# RX08c.net
KiCad netlist of a schematic drawn in EAGLE
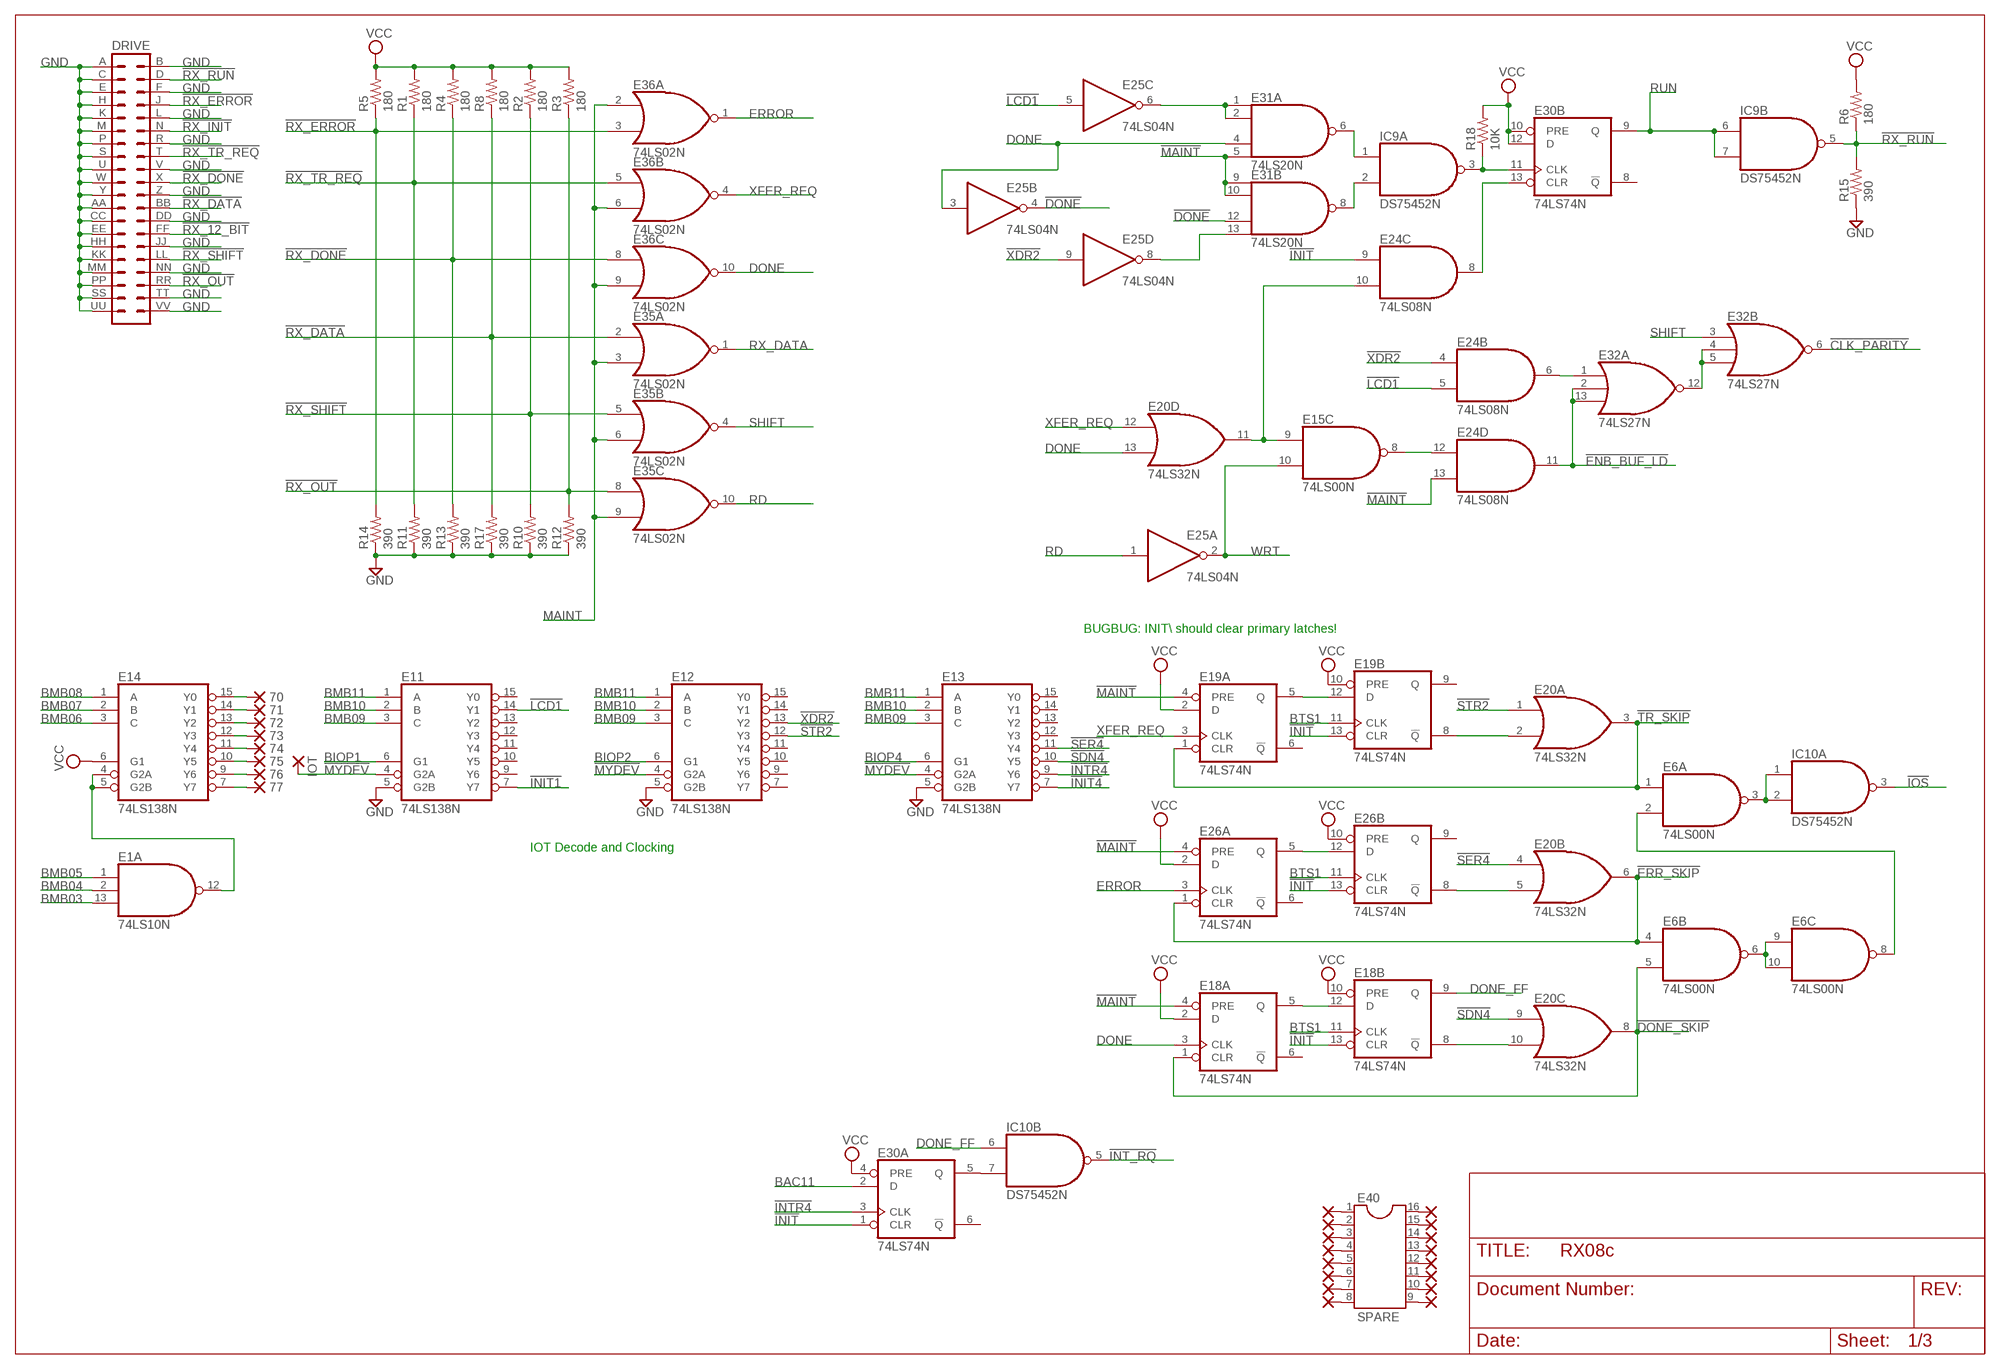
[diagram p0: schematic, sheet 1]
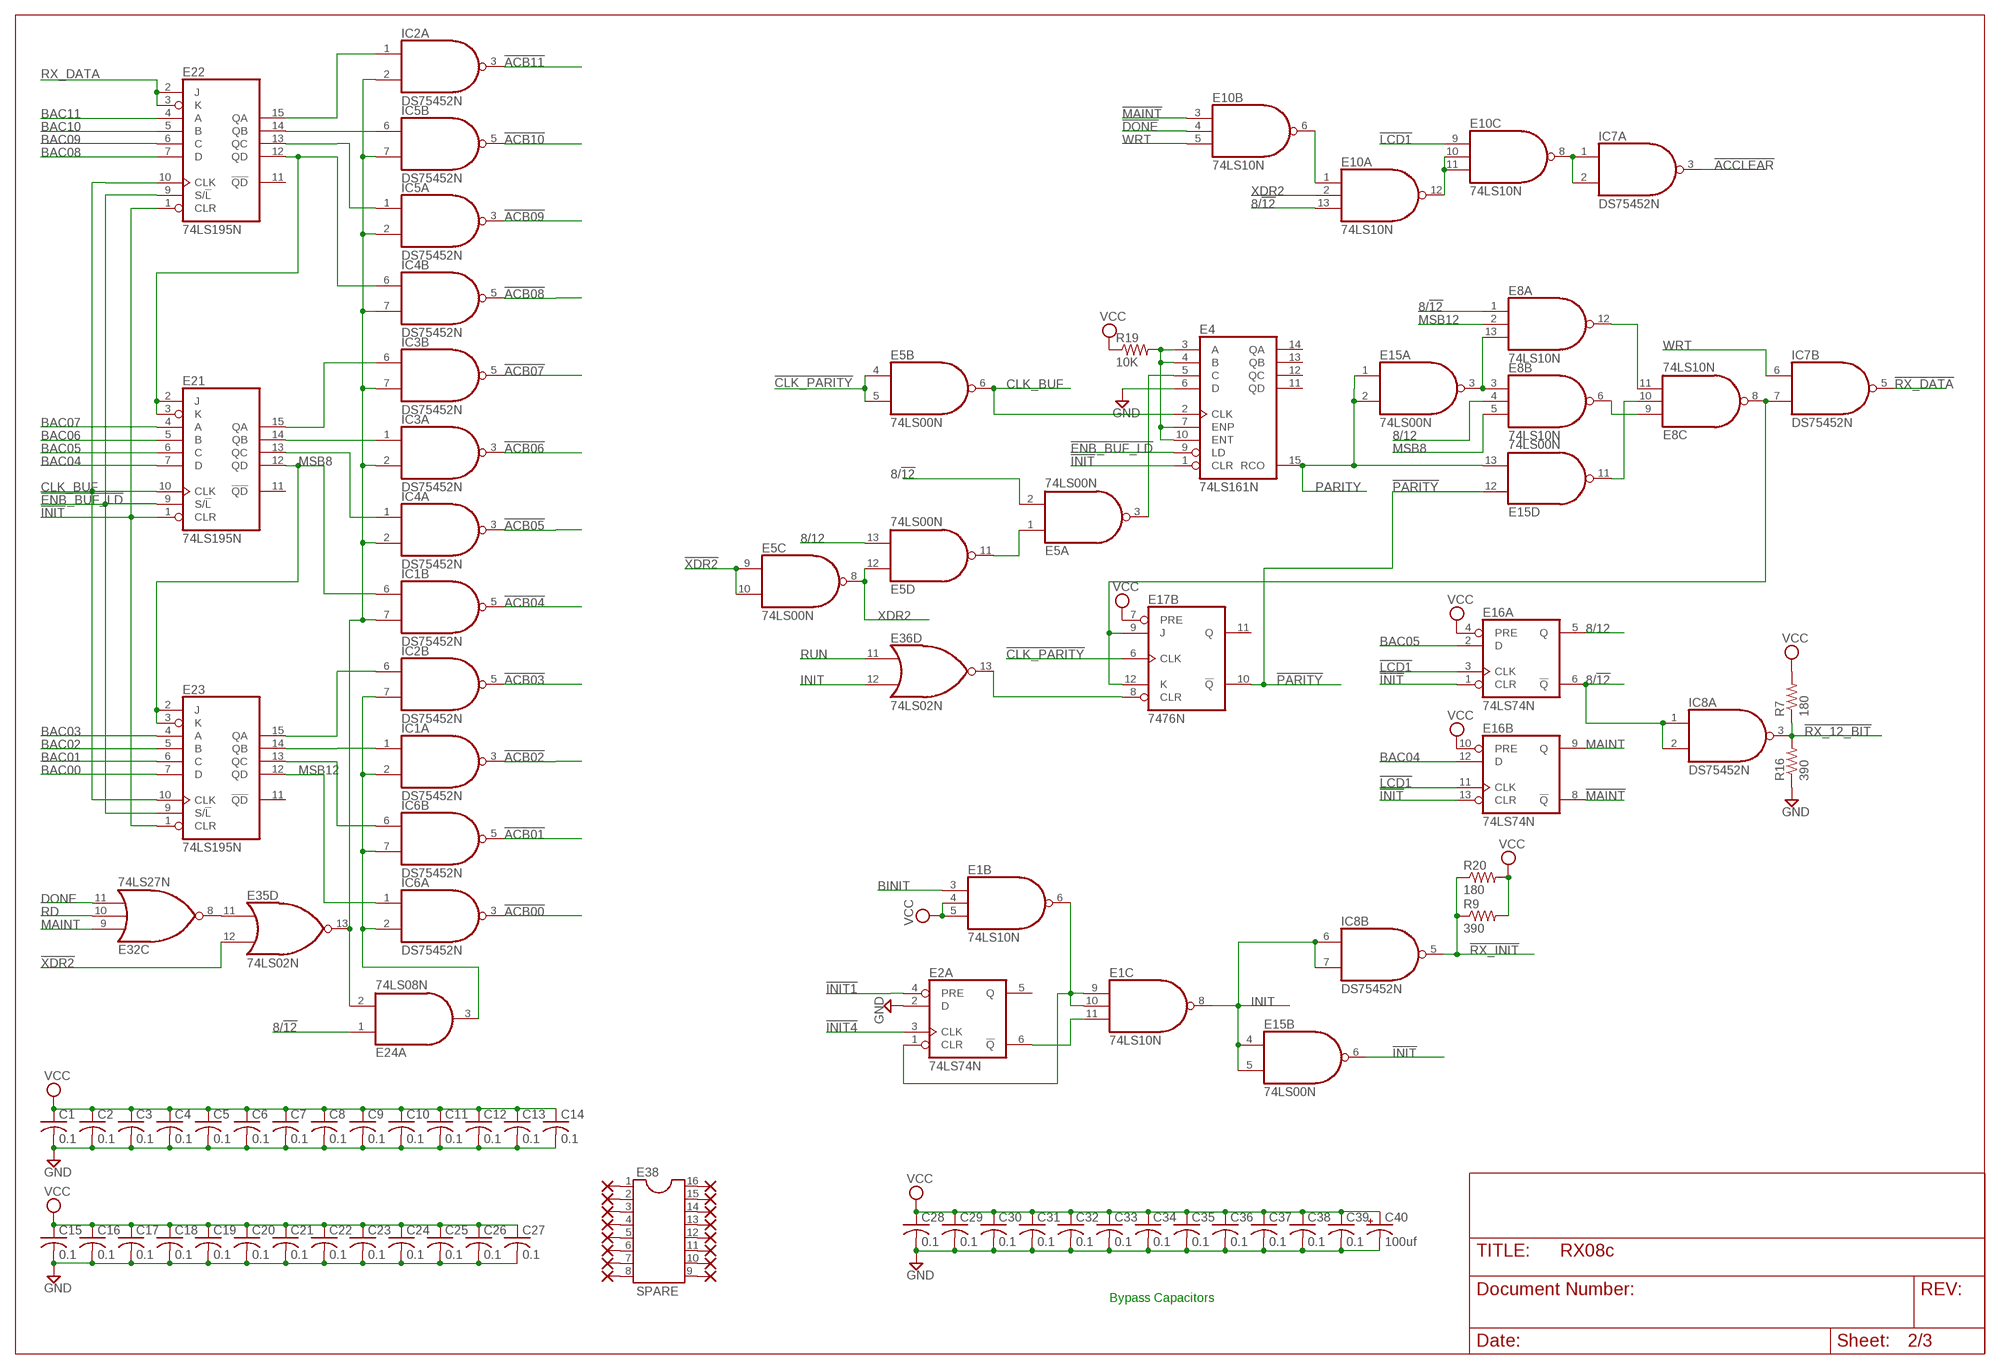
[diagram p1: schematic, sheet 2]
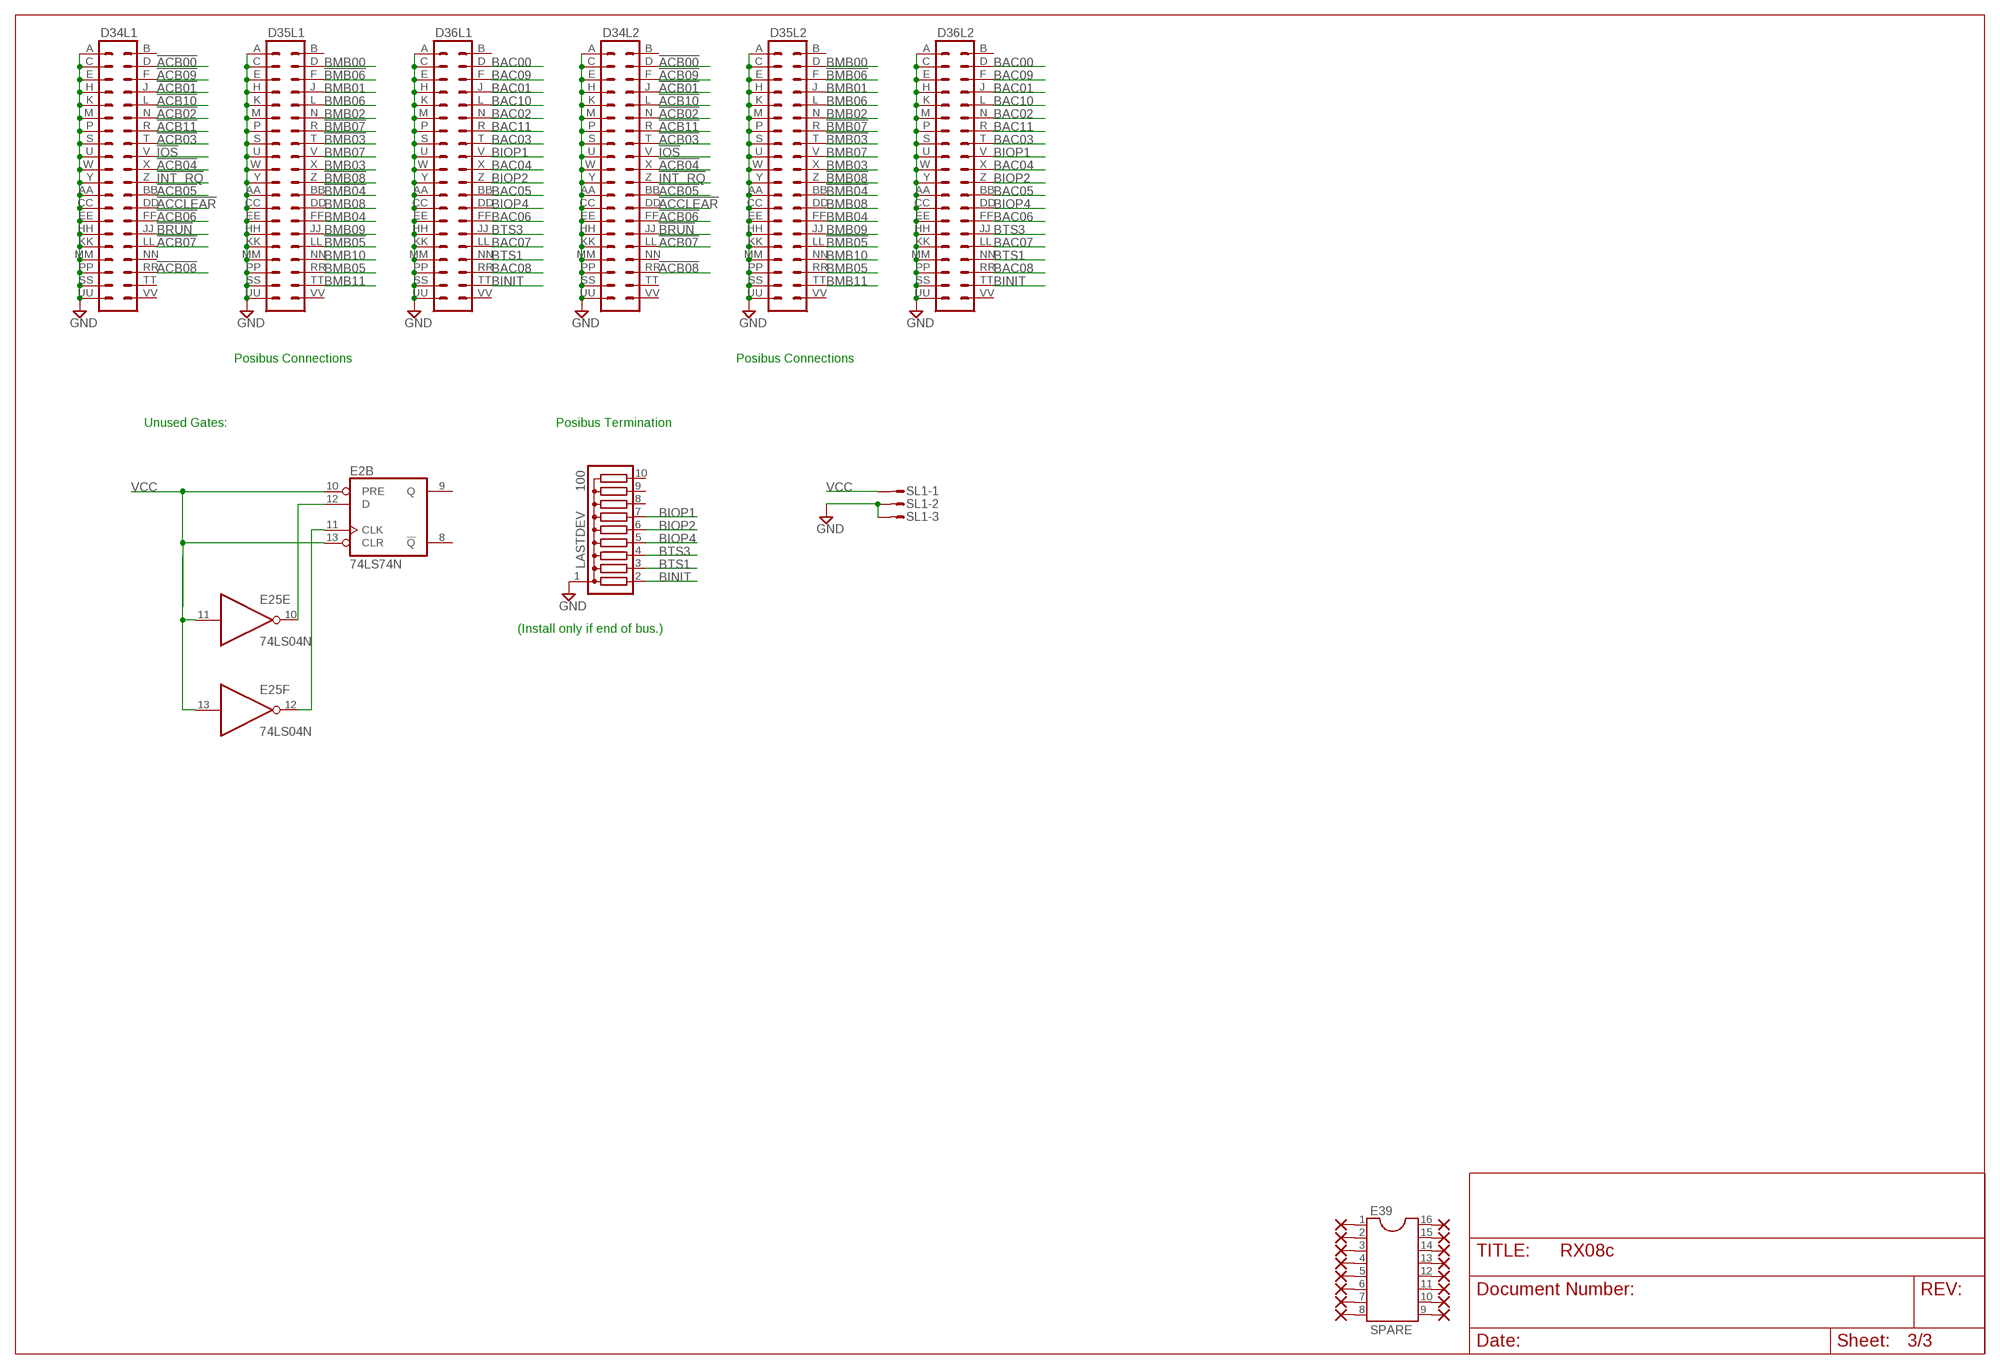
[diagram p2: schematic, sheet 3]

(export (version "E")
  (design (tool "Eeschema 10.0.6"))
  (components
    (comp (ref "C1")
      (value "0.1")
      (footprint "eagle-import:C050-025X075")
      (libsource (lib "eagle-import") (part "C-US050-025X075"))
    )
    (comp (ref "C2")
      (value "0.1")
      (footprint "eagle-import:C050-025X075")
      (libsource (lib "eagle-import") (part "C-US050-025X075"))
    )
    (comp (ref "C3")
      (value "0.1")
      (footprint "eagle-import:C050-025X075")
      (libsource (lib "eagle-import") (part "C-US050-025X075"))
    )
    (comp (ref "C4")
      (value "0.1")
      (footprint "eagle-import:C050-025X075")
      (libsource (lib "eagle-import") (part "C-US050-025X075"))
    )
    (comp (ref "C5")
      (value "0.1")
      (footprint "eagle-import:C050-025X075")
      (libsource (lib "eagle-import") (part "C-US050-025X075"))
    )
    (comp (ref "C6")
      (value "0.1")
      (footprint "eagle-import:C050-025X075")
      (libsource (lib "eagle-import") (part "C-US050-025X075"))
    )
    (comp (ref "C7")
      (value "0.1")
      (footprint "eagle-import:C050-025X075")
      (libsource (lib "eagle-import") (part "C-US050-025X075"))
    )
    (comp (ref "C8")
      (value "0.1")
      (footprint "eagle-import:C050-025X075")
      (libsource (lib "eagle-import") (part "C-US050-025X075"))
    )
    (comp (ref "C9")
      (value "0.1")
      (footprint "eagle-import:C050-025X075")
      (libsource (lib "eagle-import") (part "C-US050-025X075"))
    )
    (comp (ref "C10")
      (value "0.1")
      (footprint "eagle-import:C050-025X075")
      (libsource (lib "eagle-import") (part "C-US050-025X075"))
    )
    (comp (ref "C11")
      (value "0.1")
      (footprint "eagle-import:C050-025X075")
      (libsource (lib "eagle-import") (part "C-US050-025X075"))
    )
    (comp (ref "C12")
      (value "0.1")
      (footprint "eagle-import:C050-025X075")
      (libsource (lib "eagle-import") (part "C-US050-025X075"))
    )
    (comp (ref "C13")
      (value "0.1")
      (footprint "eagle-import:C050-025X075")
      (libsource (lib "eagle-import") (part "C-US050-025X075"))
    )
    (comp (ref "C14")
      (value "0.1")
      (footprint "eagle-import:C050-025X075")
      (libsource (lib "eagle-import") (part "C-US050-025X075"))
    )
    (comp (ref "C15")
      (value "0.1")
      (footprint "eagle-import:C050-025X075")
      (libsource (lib "eagle-import") (part "C-US050-025X075"))
    )
    (comp (ref "C16")
      (value "0.1")
      (footprint "eagle-import:C050-025X075")
      (libsource (lib "eagle-import") (part "C-US050-025X075"))
    )
    (comp (ref "C17")
      (value "0.1")
      (footprint "eagle-import:C050-025X075")
      (libsource (lib "eagle-import") (part "C-US050-025X075"))
    )
    (comp (ref "C18")
      (value "0.1")
      (footprint "eagle-import:C050-025X075")
      (libsource (lib "eagle-import") (part "C-US050-025X075"))
    )
    (comp (ref "C19")
      (value "0.1")
      (footprint "eagle-import:C050-025X075")
      (libsource (lib "eagle-import") (part "C-US050-025X075"))
    )
    (comp (ref "C20")
      (value "0.1")
      (footprint "eagle-import:C050-025X075")
      (libsource (lib "eagle-import") (part "C-US050-025X075"))
    )
    (comp (ref "C21")
      (value "0.1")
      (footprint "eagle-import:C050-025X075")
      (libsource (lib "eagle-import") (part "C-US050-025X075"))
    )
    (comp (ref "C22")
      (value "0.1")
      (footprint "eagle-import:C050-025X075")
      (libsource (lib "eagle-import") (part "C-US050-025X075"))
    )
    (comp (ref "C23")
      (value "0.1")
      (footprint "eagle-import:C050-025X075")
      (libsource (lib "eagle-import") (part "C-US050-025X075"))
    )
    (comp (ref "C24")
      (value "0.1")
      (footprint "eagle-import:C050-025X075")
      (libsource (lib "eagle-import") (part "C-US050-025X075"))
    )
    (comp (ref "C25")
      (value "0.1")
      (footprint "eagle-import:C050-025X075")
      (libsource (lib "eagle-import") (part "C-US050-025X075"))
    )
    (comp (ref "C26")
      (value "0.1")
      (footprint "eagle-import:C050-025X075")
      (libsource (lib "eagle-import") (part "C-US050-025X075"))
    )
    (comp (ref "C27")
      (value "0.1")
      (footprint "eagle-import:C050-025X075")
      (libsource (lib "eagle-import") (part "C-US050-025X075"))
    )
    (comp (ref "C28")
      (value "0.1")
      (footprint "eagle-import:C050-025X075")
      (libsource (lib "eagle-import") (part "C-US050-025X075"))
    )
    (comp (ref "C29")
      (value "0.1")
      (footprint "eagle-import:C050-025X075")
      (libsource (lib "eagle-import") (part "C-US050-025X075"))
    )
    (comp (ref "C30")
      (value "0.1")
      (footprint "eagle-import:C050-025X075")
      (libsource (lib "eagle-import") (part "C-US050-025X075"))
    )
    (comp (ref "C31")
      (value "0.1")
      (footprint "eagle-import:C050-025X075")
      (libsource (lib "eagle-import") (part "C-US050-025X075"))
    )
    (comp (ref "C32")
      (value "0.1")
      (footprint "eagle-import:C050-025X075")
      (libsource (lib "eagle-import") (part "C-US050-025X075"))
    )
    (comp (ref "C33")
      (value "0.1")
      (footprint "eagle-import:C050-025X075")
      (libsource (lib "eagle-import") (part "C-US050-025X075"))
    )
    (comp (ref "C34")
      (value "0.1")
      (footprint "eagle-import:C050-025X075")
      (libsource (lib "eagle-import") (part "C-US050-025X075"))
    )
    (comp (ref "C35")
      (value "0.1")
      (footprint "eagle-import:C050-025X075")
      (libsource (lib "eagle-import") (part "C-US050-025X075"))
    )
    (comp (ref "C36")
      (value "0.1")
      (footprint "eagle-import:C050-025X075")
      (libsource (lib "eagle-import") (part "C-US050-025X075"))
    )
    (comp (ref "C37")
      (value "0.1")
      (footprint "eagle-import:C050-025X075")
      (libsource (lib "eagle-import") (part "C-US050-025X075"))
    )
    (comp (ref "C38")
      (value "0.1")
      (footprint "eagle-import:C050-025X075")
      (libsource (lib "eagle-import") (part "C-US050-025X075"))
    )
    (comp (ref "C39")
      (value "0.1")
      (footprint "eagle-import:C050-025X075")
      (libsource (lib "eagle-import") (part "C-US050-025X075"))
    )
    (comp (ref "C40")
      (value "100uf")
      (footprint "eagle-import:E22-9")
      (libsource (lib "eagle-import") (part "CPOL-USE22-9AXIAL"))
    )
    (comp (ref "E1")
      (value "74LS10N")
      (footprint "eagle-import:DIL14")
      (libsource (lib "eagle-import") (part "7410NLS"))
    )
    (comp (ref "E2")
      (value "74LS74N")
      (footprint "eagle-import:DIL14")
      (libsource (lib "eagle-import") (part "7474NLS"))
    )
    (comp (ref "E4")
      (value "74LS161N")
      (footprint "eagle-import:DIL16")
      (libsource (lib "eagle-import") (part "74161NLS"))
    )
    (comp (ref "E5")
      (value "74LS00N")
      (footprint "eagle-import:DIL14")
      (libsource (lib "eagle-import") (part "7400NLS"))
    )
    (comp (ref "E8")
      (value "74LS10N")
      (footprint "eagle-import:DIL14")
      (libsource (lib "eagle-import") (part "7410NLS"))
    )
    (comp (ref "E10")
      (value "74LS10N")
      (footprint "eagle-import:DIL14")
      (libsource (lib "eagle-import") (part "7410NLS"))
    )
    (comp (ref "E15")
      (value "74LS00N")
      (footprint "eagle-import:DIL14")
      (libsource (lib "eagle-import") (part "7400NLS"))
    )
    (comp (ref "E16")
      (value "74LS74N")
      (footprint "eagle-import:DIL14")
      (libsource (lib "eagle-import") (part "7474NLS"))
    )
    (comp (ref "E17")
      (value "7476N")
      (footprint "eagle-import:DIL16")
      (libsource (lib "eagle-import") (part "7476N"))
    )
    (comp (ref "E21")
      (value "74LS195N")
      (footprint "eagle-import:DIL16")
      (libsource (lib "eagle-import") (part "74195NLS"))
    )
    (comp (ref "E22")
      (value "74LS195N")
      (footprint "eagle-import:DIL16")
      (libsource (lib "eagle-import") (part "74195NLS"))
    )
    (comp (ref "E23")
      (value "74LS195N")
      (footprint "eagle-import:DIL16")
      (libsource (lib "eagle-import") (part "74195NLS"))
    )
    (comp (ref "E24")
      (value "74LS08N")
      (footprint "eagle-import:DIL14")
      (libsource (lib "eagle-import") (part "7408NLS"))
    )
    (comp (ref "E32")
      (value "74LS27N")
      (footprint "eagle-import:DIL14")
      (libsource (lib "eagle-import") (part "7427NLS"))
    )
    (comp (ref "E35")
      (value "74LS02N")
      (footprint "eagle-import:DIL14")
      (libsource (lib "eagle-import") (part "7402NLS"))
    )
    (comp (ref "E36")
      (value "74LS02N")
      (footprint "eagle-import:DIL14")
      (libsource (lib "eagle-import") (part "7402NLS"))
    )
    (comp (ref "E38")
      (value "SPARE")
      (footprint "eagle-import:DIL16")
      (libsource (lib "eagle-import") (part "DIL16"))
    )
    (comp (ref "IC1")
      (value "DS75452N")
      (footprint "eagle-import:DIL08")
      (libsource (lib "eagle-import") (part "DS75452N"))
    )
    (comp (ref "IC2")
      (value "DS75452N")
      (footprint "eagle-import:DIL08")
      (libsource (lib "eagle-import") (part "DS75452N"))
    )
    (comp (ref "IC3")
      (value "DS75452N")
      (footprint "eagle-import:DIL08")
      (libsource (lib "eagle-import") (part "DS75452N"))
    )
    (comp (ref "IC4")
      (value "DS75452N")
      (footprint "eagle-import:DIL08")
      (libsource (lib "eagle-import") (part "DS75452N"))
    )
    (comp (ref "IC5")
      (value "DS75452N")
      (footprint "eagle-import:DIL08")
      (libsource (lib "eagle-import") (part "DS75452N"))
    )
    (comp (ref "IC6")
      (value "DS75452N")
      (footprint "eagle-import:DIL08")
      (libsource (lib "eagle-import") (part "DS75452N"))
    )
    (comp (ref "IC7")
      (value "DS75452N")
      (footprint "eagle-import:DIL08")
      (libsource (lib "eagle-import") (part "DS75452N"))
    )
    (comp (ref "IC8")
      (value "DS75452N")
      (footprint "eagle-import:DIL08")
      (libsource (lib "eagle-import") (part "DS75452N"))
    )
    (comp (ref "PAD10")
      (value "1,6/0,8")
      (footprint "eagle-import:1,6_0,8")
      (libsource (lib "eagle-import") (part "1,6/0,8"))
    )
    (comp (ref "PAD11")
      (value "1,6/0,8")
      (footprint "eagle-import:1,6_0,8")
      (libsource (lib "eagle-import") (part "1,6/0,8"))
    )
    (comp (ref "PAD12")
      (value "1,6/0,8")
      (footprint "eagle-import:1,6_0,8")
      (libsource (lib "eagle-import") (part "1,6/0,8"))
    )
    (comp (ref "PAD13")
      (value "1,6/0,8")
      (footprint "eagle-import:1,6_0,8")
      (libsource (lib "eagle-import") (part "1,6/0,8"))
    )
    (comp (ref "PAD14")
      (value "1,6/0,8")
      (footprint "eagle-import:1,6_0,8")
      (libsource (lib "eagle-import") (part "1,6/0,8"))
    )
    (comp (ref "PAD15")
      (value "1,6/0,8")
      (footprint "eagle-import:1,6_0,8")
      (libsource (lib "eagle-import") (part "1,6/0,8"))
    )
    (comp (ref "PAD16")
      (value "1,6/0,8")
      (footprint "eagle-import:1,6_0,8")
      (libsource (lib "eagle-import") (part "1,6/0,8"))
    )
    (comp (ref "PAD17")
      (value "1,6/0,8")
      (footprint "eagle-import:1,6_0,8")
      (libsource (lib "eagle-import") (part "1,6/0,8"))
    )
    (comp (ref "PAD20")
      (value "1,6/0,8")
      (footprint "eagle-import:1,6_0,8")
      (libsource (lib "eagle-import") (part "1,6/0,8"))
    )
    (comp (ref "PAD21")
      (value "1,6/0,8")
      (footprint "eagle-import:1,6_0,8")
      (libsource (lib "eagle-import") (part "1,6/0,8"))
    )
    (comp (ref "PAD22")
      (value "1,6/0,8")
      (footprint "eagle-import:1,6_0,8")
      (libsource (lib "eagle-import") (part "1,6/0,8"))
    )
    (comp (ref "PAD23")
      (value "1,6/0,8")
      (footprint "eagle-import:1,6_0,8")
      (libsource (lib "eagle-import") (part "1,6/0,8"))
    )
    (comp (ref "PAD24")
      (value "1,6/0,8")
      (footprint "eagle-import:1,6_0,8")
      (libsource (lib "eagle-import") (part "1,6/0,8"))
    )
    (comp (ref "PAD25")
      (value "1,6/0,8")
      (footprint "eagle-import:1,6_0,8")
      (libsource (lib "eagle-import") (part "1,6/0,8"))
    )
    (comp (ref "PAD26")
      (value "1,6/0,8")
      (footprint "eagle-import:1,6_0,8")
      (libsource (lib "eagle-import") (part "1,6/0,8"))
    )
    (comp (ref "PAD27")
      (value "1,6/0,8")
      (footprint "eagle-import:1,6_0,8")
      (libsource (lib "eagle-import") (part "1,6/0,8"))
    )
    (comp (ref "R7")
      (value "180")
      (footprint "eagle-import:0207_10")
      (libsource (lib "eagle-import") (part "R-US_0207/10"))
    )
    (comp (ref "R9")
      (value "390")
      (footprint "eagle-import:0207_10")
      (libsource (lib "eagle-import") (part "R-US_0207/10"))
    )
    (comp (ref "R16")
      (value "390")
      (footprint "eagle-import:0207_10")
      (libsource (lib "eagle-import") (part "R-US_0207/10"))
    )
    (comp (ref "R19")
      (value "10K")
      (footprint "eagle-import:0207_10")
      (libsource (lib "eagle-import") (part "R-US_0207/10"))
    )
    (comp (ref "R20")
      (value "180")
      (footprint "eagle-import:0207_10")
      (libsource (lib "eagle-import") (part "R-US_0207/10"))
    )
    (comp (ref "D34L1")
      (value "DEC40PINV")
      (footprint "eagle-import:DEC40PINV")
      (libsource (lib "eagle-import") (part "DEC40PINV"))
    )
    (comp (ref "D34L2")
      (value "DEC40PINV")
      (footprint "eagle-import:DEC40PINV")
      (libsource (lib "eagle-import") (part "DEC40PINV"))
    )
    (comp (ref "D35L1")
      (value "DEC40PINV")
      (footprint "eagle-import:DEC40PINV")
      (libsource (lib "eagle-import") (part "DEC40PINV"))
    )
    (comp (ref "D35L2")
      (value "DEC40PINV")
      (footprint "eagle-import:DEC40PINV")
      (libsource (lib "eagle-import") (part "DEC40PINV"))
    )
    (comp (ref "D36L1")
      (value "DEC40PINV")
      (footprint "eagle-import:DEC40PINV")
      (libsource (lib "eagle-import") (part "DEC40PINV"))
    )
    (comp (ref "D36L2")
      (value "DEC40PINV")
      (footprint "eagle-import:DEC40PINV")
      (libsource (lib "eagle-import") (part "DEC40PINV"))
    )
    (comp (ref "E25")
      (value "74LS04N")
      (footprint "eagle-import:DIL14")
      (libsource (lib "eagle-import") (part "7404NLS"))
    )
    (comp (ref "E39")
      (value "SPARE")
      (footprint "eagle-import:DIL16")
      (libsource (lib "eagle-import") (part "DIL16"))
    )
    (comp (ref "LASTDEV")
      (value "100")
      (footprint "eagle-import:SIL10")
      (libsource (lib "eagle-import") (part "G09R"))
    )
    (comp (ref "PAD42")
      (value "1,6/0,8")
      (footprint "eagle-import:1,6_0,8")
      (libsource (lib "eagle-import") (part "1,6/0,8"))
    )
    (comp (ref "PAD43")
      (value "1,6/0,8")
      (footprint "eagle-import:1,6_0,8")
      (libsource (lib "eagle-import") (part "1,6/0,8"))
    )
    (comp (ref "PAD44")
      (value "1,6/0,8")
      (footprint "eagle-import:1,6_0,8")
      (libsource (lib "eagle-import") (part "1,6/0,8"))
    )
    (comp (ref "PAD45")
      (value "1,6/0,8")
      (footprint "eagle-import:1,6_0,8")
      (libsource (lib "eagle-import") (part "1,6/0,8"))
    )
    (comp (ref "PAD46")
      (value "1,6/0,8")
      (footprint "eagle-import:1,6_0,8")
      (libsource (lib "eagle-import") (part "1,6/0,8"))
    )
    (comp (ref "PAD47")
      (value "1,6/0,8")
      (footprint "eagle-import:1,6_0,8")
      (libsource (lib "eagle-import") (part "1,6/0,8"))
    )
    (comp (ref "PAD48")
      (value "1,6/0,8")
      (footprint "eagle-import:1,6_0,8")
      (libsource (lib "eagle-import") (part "1,6/0,8"))
    )
    (comp (ref "PAD49")
      (value "1,6/0,8")
      (footprint "eagle-import:1,6_0,8")
      (libsource (lib "eagle-import") (part "1,6/0,8"))
    )
    (comp (ref "PAD50")
      (value "1,6/0,8")
      (footprint "eagle-import:1,6_0,8")
      (libsource (lib "eagle-import") (part "1,6/0,8"))
    )
    (comp (ref "PAD51")
      (value "1,6/0,8")
      (footprint "eagle-import:1,6_0,8")
      (libsource (lib "eagle-import") (part "1,6/0,8"))
    )
    (comp (ref "PAD52")
      (value "1,6/0,8")
      (footprint "eagle-import:1,6_0,8")
      (libsource (lib "eagle-import") (part "1,6/0,8"))
    )
    (comp (ref "PAD53")
      (value "1,6/0,8")
      (footprint "eagle-import:1,6_0,8")
      (libsource (lib "eagle-import") (part "1,6/0,8"))
    )
    (comp (ref "PAD54")
      (value "1,6/0,8")
      (footprint "eagle-import:1,6_0,8")
      (libsource (lib "eagle-import") (part "1,6/0,8"))
    )
    (comp (ref "PAD55")
      (value "1,6/0,8")
      (footprint "eagle-import:1,6_0,8")
      (libsource (lib "eagle-import") (part "1,6/0,8"))
    )
    (comp (ref "PAD56")
      (value "1,6/0,8")
      (footprint "eagle-import:1,6_0,8")
      (libsource (lib "eagle-import") (part "1,6/0,8"))
    )
    (comp (ref "PAD57")
      (value "1,6/0,8")
      (footprint "eagle-import:1,6_0,8")
      (libsource (lib "eagle-import") (part "1,6/0,8"))
    )
    (comp (ref "SL1")
      (value "MA04S")
      (footprint "eagle-import:04PA")
      (libsource (lib "eagle-import") (part "MA04S"))
    )
    (comp (ref "70")
      (value "1,6/0,8")
      (footprint "eagle-import:1,6_0,8")
      (libsource (lib "eagle-import") (part "1,6/0,8"))
    )
    (comp (ref "71")
      (value "1,6/0,8")
      (footprint "eagle-import:1,6_0,8")
      (libsource (lib "eagle-import") (part "1,6/0,8"))
    )
    (comp (ref "72")
      (value "1,6/0,8")
      (footprint "eagle-import:1,6_0,8")
      (libsource (lib "eagle-import") (part "1,6/0,8"))
    )
    (comp (ref "73")
      (value "1,6/0,8")
      (footprint "eagle-import:1,6_0,8")
      (libsource (lib "eagle-import") (part "1,6/0,8"))
    )
    (comp (ref "74")
      (value "1,6/0,8")
      (footprint "eagle-import:1,6_0,8")
      (libsource (lib "eagle-import") (part "1,6/0,8"))
    )
    (comp (ref "75")
      (value "1,6/0,8")
      (footprint "eagle-import:1,6_0,8")
      (libsource (lib "eagle-import") (part "1,6/0,8"))
    )
    (comp (ref "76")
      (value "1,6/0,8")
      (footprint "eagle-import:1,6_0,8")
      (libsource (lib "eagle-import") (part "1,6/0,8"))
    )
    (comp (ref "77")
      (value "1,6/0,8")
      (footprint "eagle-import:1,6_0,8")
      (libsource (lib "eagle-import") (part "1,6/0,8"))
    )
    (comp (ref "DRIVE")
      (value "DEC40PINV")
      (footprint "eagle-import:DEC40PINV")
      (libsource (lib "eagle-import") (part "DEC40PINV"))
    )
    (comp (ref "E6")
      (value "74LS00N")
      (footprint "eagle-import:DIL14")
      (libsource (lib "eagle-import") (part "7400NLS"))
    )
    (comp (ref "E11")
      (value "74LS138N")
      (footprint "eagle-import:DIL16")
      (libsource (lib "eagle-import") (part "74138NLS"))
    )
    (comp (ref "E12")
      (value "74LS138N")
      (footprint "eagle-import:DIL16")
      (libsource (lib "eagle-import") (part "74138NLS"))
    )
    (comp (ref "E13")
      (value "74LS138N")
      (footprint "eagle-import:DIL16")
      (libsource (lib "eagle-import") (part "74138NLS"))
    )
    (comp (ref "E14")
      (value "74LS138N")
      (footprint "eagle-import:DIL16")
      (libsource (lib "eagle-import") (part "74138NLS"))
    )
    (comp (ref "E18")
      (value "74LS74N")
      (footprint "eagle-import:DIL14")
      (libsource (lib "eagle-import") (part "7474NLS"))
    )
    (comp (ref "E19")
      (value "74LS74N")
      (footprint "eagle-import:DIL14")
      (libsource (lib "eagle-import") (part "7474NLS"))
    )
    (comp (ref "E20")
      (value "74LS32N")
      (footprint "eagle-import:DIL14")
      (libsource (lib "eagle-import") (part "7432NLS"))
    )
    (comp (ref "E26")
      (value "74LS74N")
      (footprint "eagle-import:DIL14")
      (libsource (lib "eagle-import") (part "7474NLS"))
    )
    (comp (ref "E30")
      (value "74LS74N")
      (footprint "eagle-import:DIL14")
      (libsource (lib "eagle-import") (part "7474NLS"))
    )
    (comp (ref "E31")
      (value "74LS20N")
      (footprint "eagle-import:DIL14")
      (libsource (lib "eagle-import") (part "7420NLS"))
    )
    (comp (ref "E40")
      (value "SPARE")
      (footprint "eagle-import:DIL16")
      (libsource (lib "eagle-import") (part "DIL16"))
    )
    (comp (ref "IC9")
      (value "DS75452N")
      (footprint "eagle-import:DIL08")
      (libsource (lib "eagle-import") (part "DS75452N"))
    )
    (comp (ref "IC10")
      (value "DS75452N")
      (footprint "eagle-import:DIL08")
      (libsource (lib "eagle-import") (part "DS75452N"))
    )
    (comp (ref "IOT")
      (value "1,6/0,8")
      (footprint "eagle-import:1,6_0,8")
      (libsource (lib "eagle-import") (part "1,6/0,8"))
    )
    (comp (ref "PAD18")
      (value "1,6/0,8")
      (footprint "eagle-import:1,6_0,8")
      (libsource (lib "eagle-import") (part "1,6/0,8"))
    )
    (comp (ref "PAD19")
      (value "1,6/0,8")
      (footprint "eagle-import:1,6_0,8")
      (libsource (lib "eagle-import") (part "1,6/0,8"))
    )
    (comp (ref "PAD28")
      (value "1,6/0,8")
      (footprint "eagle-import:1,6_0,8")
      (libsource (lib "eagle-import") (part "1,6/0,8"))
    )
    (comp (ref "PAD29")
      (value "1,6/0,8")
      (footprint "eagle-import:1,6_0,8")
      (libsource (lib "eagle-import") (part "1,6/0,8"))
    )
    (comp (ref "PAD30")
      (value "1,6/0,8")
      (footprint "eagle-import:1,6_0,8")
      (libsource (lib "eagle-import") (part "1,6/0,8"))
    )
    (comp (ref "PAD31")
      (value "1,6/0,8")
      (footprint "eagle-import:1,6_0,8")
      (libsource (lib "eagle-import") (part "1,6/0,8"))
    )
    (comp (ref "PAD32")
      (value "1,6/0,8")
      (footprint "eagle-import:1,6_0,8")
      (libsource (lib "eagle-import") (part "1,6/0,8"))
    )
    (comp (ref "PAD33")
      (value "1,6/0,8")
      (footprint "eagle-import:1,6_0,8")
      (libsource (lib "eagle-import") (part "1,6/0,8"))
    )
    (comp (ref "PAD34")
      (value "1,6/0,8")
      (footprint "eagle-import:1,6_0,8")
      (libsource (lib "eagle-import") (part "1,6/0,8"))
    )
    (comp (ref "PAD35")
      (value "1,6/0,8")
      (footprint "eagle-import:1,6_0,8")
      (libsource (lib "eagle-import") (part "1,6/0,8"))
    )
    (comp (ref "PAD36")
      (value "1,6/0,8")
      (footprint "eagle-import:1,6_0,8")
      (libsource (lib "eagle-import") (part "1,6/0,8"))
    )
    (comp (ref "PAD37")
      (value "1,6/0,8")
      (footprint "eagle-import:1,6_0,8")
      (libsource (lib "eagle-import") (part "1,6/0,8"))
    )
    (comp (ref "PAD38")
      (value "1,6/0,8")
      (footprint "eagle-import:1,6_0,8")
      (libsource (lib "eagle-import") (part "1,6/0,8"))
    )
    (comp (ref "PAD39")
      (value "1,6/0,8")
      (footprint "eagle-import:1,6_0,8")
      (libsource (lib "eagle-import") (part "1,6/0,8"))
    )
    (comp (ref "PAD40")
      (value "1,6/0,8")
      (footprint "eagle-import:1,6_0,8")
      (libsource (lib "eagle-import") (part "1,6/0,8"))
    )
    (comp (ref "PAD41")
      (value "1,6/0,8")
      (footprint "eagle-import:1,6_0,8")
      (libsource (lib "eagle-import") (part "1,6/0,8"))
    )
    (comp (ref "R1")
      (value "180")
      (footprint "eagle-import:0207_10")
      (libsource (lib "eagle-import") (part "R-US_0207/10"))
    )
    (comp (ref "R2")
      (value "180")
      (footprint "eagle-import:0207_10")
      (libsource (lib "eagle-import") (part "R-US_0207/10"))
    )
    (comp (ref "R3")
      (value "180")
      (footprint "eagle-import:0207_10")
      (libsource (lib "eagle-import") (part "R-US_0207/10"))
    )
    (comp (ref "R4")
      (value "180")
      (footprint "eagle-import:0207_10")
      (libsource (lib "eagle-import") (part "R-US_0207/10"))
    )
    (comp (ref "R5")
      (value "180")
      (footprint "eagle-import:0207_10")
      (libsource (lib "eagle-import") (part "R-US_0207/10"))
    )
    (comp (ref "R6")
      (value "180")
      (footprint "eagle-import:0207_10")
      (libsource (lib "eagle-import") (part "R-US_0207/10"))
    )
    (comp (ref "R8")
      (value "180")
      (footprint "eagle-import:0207_10")
      (libsource (lib "eagle-import") (part "R-US_0207/10"))
    )
    (comp (ref "R10")
      (value "390")
      (footprint "eagle-import:0207_10")
      (libsource (lib "eagle-import") (part "R-US_0207/10"))
    )
    (comp (ref "R11")
      (value "390")
      (footprint "eagle-import:0207_10")
      (libsource (lib "eagle-import") (part "R-US_0207/10"))
    )
    (comp (ref "R12")
      (value "390")
      (footprint "eagle-import:0207_10")
      (libsource (lib "eagle-import") (part "R-US_0207/10"))
    )
    (comp (ref "R13")
      (value "390")
      (footprint "eagle-import:0207_10")
      (libsource (lib "eagle-import") (part "R-US_0207/10"))
    )
    (comp (ref "R14")
      (value "390")
      (footprint "eagle-import:0207_10")
      (libsource (lib "eagle-import") (part "R-US_0207/10"))
    )
    (comp (ref "R15")
      (value "390")
      (footprint "eagle-import:0207_10")
      (libsource (lib "eagle-import") (part "R-US_0207/10"))
    )
    (comp (ref "R17")
      (value "390")
      (footprint "eagle-import:0207_10")
      (libsource (lib "eagle-import") (part "R-US_0207/10"))
    )
    (comp (ref "R18")
      (value "10K")
      (footprint "eagle-import:0207_10")
      (libsource (lib "eagle-import") (part "R-US_0207/10"))
    )
  )
  (nets
    (net (code "1") (name "8{slash}12") (class "Default")
      (node (ref "E16") (pin "5") (pinfunction "Q_5") (pintype "output"))
      (node (ref "E5") (pin "13") (pinfunction "I1_13") (pintype "input"))
      (node (ref "E8") (pin "4") (pinfunction "I1_4") (pintype "input"))
    )
    (net (code "2") (name "8{slash}~{12}") (class "Default")
      (node (ref "E10") (pin "13") (pinfunction "I2_13") (pintype "input"))
      (node (ref "E16") (pin "6") (pinfunction "~{Q}_6") (pintype "output"))
      (node (ref "E24") (pin "1") (pinfunction "I0_1") (pintype "input"))
      (node (ref "E5") (pin "2") (pinfunction "I1_2") (pintype "input"))
      (node (ref "E8") (pin "1") (pinfunction "I0_1") (pintype "input"))
      (node (ref "IC8") (pin "1") (pinfunction "I0_1") (pintype "input"))
      (node (ref "IC8") (pin "2") (pinfunction "I1_2") (pintype "input"))
    )
    (net (code "3") (name "BAC00") (class "Default")
      (node (ref "D36L1") (pin "D") (pinfunction "4_D") (pintype "bidirectional"))
      (node (ref "D36L2") (pin "D") (pinfunction "4_D") (pintype "bidirectional"))
      (node (ref "E23") (pin "7") (pinfunction "D_7") (pintype "input"))
    )
    (net (code "4") (name "BAC01") (class "Default")
      (node (ref "D36L1") (pin "J") (pinfunction "8_J") (pintype "bidirectional"))
      (node (ref "D36L2") (pin "J") (pinfunction "8_J") (pintype "bidirectional"))
      (node (ref "E23") (pin "6") (pinfunction "C_6") (pintype "input"))
    )
    (net (code "5") (name "BAC02") (class "Default")
      (node (ref "D36L1") (pin "N") (pinfunction "12_N") (pintype "bidirectional"))
      (node (ref "D36L2") (pin "N") (pinfunction "12_N") (pintype "bidirectional"))
      (node (ref "E23") (pin "5") (pinfunction "B_5") (pintype "input"))
    )
    (net (code "6") (name "BAC03") (class "Default")
      (node (ref "D36L1") (pin "T") (pinfunction "16_T") (pintype "bidirectional"))
      (node (ref "D36L2") (pin "T") (pinfunction "16_T") (pintype "bidirectional"))
      (node (ref "E23") (pin "4") (pinfunction "A_4") (pintype "input"))
    )
    (net (code "7") (name "BAC04") (class "Default")
      (node (ref "D36L1") (pin "X") (pinfunction "20_X") (pintype "bidirectional"))
      (node (ref "D36L2") (pin "X") (pinfunction "20_X") (pintype "bidirectional"))
      (node (ref "E16") (pin "12") (pinfunction "D_12") (pintype "input"))
      (node (ref "E21") (pin "7") (pinfunction "D_7") (pintype "input"))
    )
    (net (code "8") (name "BAC05") (class "Default")
      (node (ref "D36L1") (pin "BB") (pinfunction "24_BB") (pintype "bidirectional"))
      (node (ref "D36L2") (pin "BB") (pinfunction "24_BB") (pintype "bidirectional"))
      (node (ref "E16") (pin "2") (pinfunction "D_2") (pintype "input"))
      (node (ref "E21") (pin "6") (pinfunction "C_6") (pintype "input"))
    )
    (net (code "9") (name "BAC06") (class "Default")
      (node (ref "D36L1") (pin "FF") (pinfunction "28_FF") (pintype "bidirectional"))
      (node (ref "D36L2") (pin "FF") (pinfunction "28_FF") (pintype "bidirectional"))
      (node (ref "E21") (pin "5") (pinfunction "B_5") (pintype "input"))
    )
    (net (code "10") (name "BAC07") (class "Default")
      (node (ref "D36L1") (pin "LL") (pinfunction "32_LL") (pintype "bidirectional"))
      (node (ref "D36L2") (pin "LL") (pinfunction "32_LL") (pintype "bidirectional"))
      (node (ref "E21") (pin "4") (pinfunction "A_4") (pintype "input"))
    )
    (net (code "11") (name "BAC08") (class "Default")
      (node (ref "D36L1") (pin "RR") (pinfunction "36_RR") (pintype "bidirectional"))
      (node (ref "D36L2") (pin "RR") (pinfunction "36_RR") (pintype "bidirectional"))
      (node (ref "E22") (pin "7") (pinfunction "D_7") (pintype "input"))
    )
    (net (code "12") (name "BAC09") (class "Default")
      (node (ref "D36L1") (pin "F") (pinfunction "6_F") (pintype "bidirectional"))
      (node (ref "D36L2") (pin "F") (pinfunction "6_F") (pintype "bidirectional"))
      (node (ref "E22") (pin "6") (pinfunction "C_6") (pintype "input"))
    )
    (net (code "13") (name "BAC10") (class "Default")
      (node (ref "D36L1") (pin "L") (pinfunction "10_L") (pintype "bidirectional"))
      (node (ref "D36L2") (pin "L") (pinfunction "10_L") (pintype "bidirectional"))
      (node (ref "E22") (pin "5") (pinfunction "B_5") (pintype "input"))
    )
    (net (code "14") (name "BAC11") (class "Default")
      (node (ref "D36L1") (pin "R") (pinfunction "14_R") (pintype "bidirectional"))
      (node (ref "D36L2") (pin "R") (pinfunction "14_R") (pintype "bidirectional"))
      (node (ref "E22") (pin "4") (pinfunction "A_4") (pintype "input"))
      (node (ref "E30") (pin "2") (pinfunction "D_2") (pintype "input"))
    )
    (net (code "15") (name "BINIT") (class "Default")
      (node (ref "D36L1") (pin "TT") (pinfunction "38_TT") (pintype "bidirectional"))
      (node (ref "D36L2") (pin "TT") (pinfunction "38_TT") (pintype "bidirectional"))
      (node (ref "E1") (pin "3") (pinfunction "I0_3") (pintype "input"))
      (node (ref "LASTDEV") (pin "2") (pinfunction "2_2") (pintype "passive"))
    )
    (net (code "16") (name "BIOP1") (class "Default")
      (node (ref "D36L1") (pin "V") (pinfunction "18_V") (pintype "bidirectional"))
      (node (ref "D36L2") (pin "V") (pinfunction "18_V") (pintype "bidirectional"))
      (node (ref "E11") (pin "6") (pinfunction "G1_6") (pintype "input"))
      (node (ref "LASTDEV") (pin "7") (pinfunction "7_7") (pintype "passive"))
    )
    (net (code "17") (name "BIOP2") (class "Default")
      (node (ref "D36L1") (pin "Z") (pinfunction "22_Z") (pintype "bidirectional"))
      (node (ref "D36L2") (pin "Z") (pinfunction "22_Z") (pintype "bidirectional"))
      (node (ref "E12") (pin "6") (pinfunction "G1_6") (pintype "input"))
      (node (ref "LASTDEV") (pin "6") (pinfunction "6_6") (pintype "passive"))
    )
    (net (code "18") (name "BIOP4") (class "Default")
      (node (ref "D36L1") (pin "DD") (pinfunction "26_DD") (pintype "bidirectional"))
      (node (ref "D36L2") (pin "DD") (pinfunction "26_DD") (pintype "bidirectional"))
      (node (ref "E13") (pin "6") (pinfunction "G1_6") (pintype "input"))
      (node (ref "LASTDEV") (pin "5") (pinfunction "5_5") (pintype "passive"))
    )
    (net (code "19") (name "BMB00") (class "Default")
      (node (ref "D35L1") (pin "D") (pinfunction "4_D") (pintype "bidirectional"))
      (node (ref "D35L2") (pin "D") (pinfunction "4_D") (pintype "bidirectional"))
    )
    (net (code "20") (name "BMB01") (class "Default")
      (node (ref "D35L1") (pin "J") (pinfunction "8_J") (pintype "bidirectional"))
      (node (ref "D35L2") (pin "J") (pinfunction "8_J") (pintype "bidirectional"))
    )
    (net (code "21") (name "BMB02") (class "Default")
      (node (ref "D35L1") (pin "N") (pinfunction "12_N") (pintype "bidirectional"))
      (node (ref "D35L2") (pin "N") (pinfunction "12_N") (pintype "bidirectional"))
    )
    (net (code "22") (name "BMB03") (class "Default")
      (node (ref "D35L1") (pin "X") (pinfunction "20_X") (pintype "bidirectional"))
      (node (ref "D35L2") (pin "X") (pinfunction "20_X") (pintype "bidirectional"))
      (node (ref "E1") (pin "13") (pinfunction "I2_13") (pintype "input"))
    )
    (net (code "23") (name "BMB04") (class "Default")
      (node (ref "D35L1") (pin "FF") (pinfunction "28_FF") (pintype "bidirectional"))
      (node (ref "D35L2") (pin "FF") (pinfunction "28_FF") (pintype "bidirectional"))
      (node (ref "E1") (pin "2") (pinfunction "I1_2") (pintype "input"))
    )
    (net (code "24") (name "BMB05") (class "Default")
      (node (ref "D35L1") (pin "RR") (pinfunction "36_RR") (pintype "bidirectional"))
      (node (ref "D35L2") (pin "RR") (pinfunction "36_RR") (pintype "bidirectional"))
      (node (ref "E1") (pin "1") (pinfunction "I0_1") (pintype "input"))
    )
    (net (code "25") (name "BMB06") (class "Default")
      (node (ref "D35L1") (pin "L") (pinfunction "10_L") (pintype "bidirectional"))
      (node (ref "D35L2") (pin "L") (pinfunction "10_L") (pintype "bidirectional"))
      (node (ref "E14") (pin "3") (pinfunction "C_3") (pintype "input"))
    )
    (net (code "26") (name "BMB07") (class "Default")
      (node (ref "D35L1") (pin "V") (pinfunction "18_V") (pintype "bidirectional"))
      (node (ref "D35L2") (pin "V") (pinfunction "18_V") (pintype "bidirectional"))
      (node (ref "E14") (pin "2") (pinfunction "B_2") (pintype "input"))
    )
    (net (code "27") (name "BMB08") (class "Default")
      (node (ref "D35L1") (pin "DD") (pinfunction "26_DD") (pintype "bidirectional"))
      (node (ref "D35L2") (pin "DD") (pinfunction "26_DD") (pintype "bidirectional"))
      (node (ref "E14") (pin "1") (pinfunction "A_1") (pintype "input"))
    )
    (net (code "28") (name "BMB09") (class "Default")
      (node (ref "D35L1") (pin "JJ") (pinfunction "30_JJ") (pintype "bidirectional"))
      (node (ref "D35L2") (pin "JJ") (pinfunction "30_JJ") (pintype "bidirectional"))
      (node (ref "E11") (pin "3") (pinfunction "C_3") (pintype "input"))
      (node (ref "E12") (pin "3") (pinfunction "C_3") (pintype "input"))
      (node (ref "E13") (pin "3") (pinfunction "C_3") (pintype "input"))
    )
    (net (code "29") (name "BMB10") (class "Default")
      (node (ref "D35L1") (pin "NN") (pinfunction "34_NN") (pintype "bidirectional"))
      (node (ref "D35L2") (pin "NN") (pinfunction "34_NN") (pintype "bidirectional"))
      (node (ref "E11") (pin "2") (pinfunction "B_2") (pintype "input"))
      (node (ref "E12") (pin "2") (pinfunction "B_2") (pintype "input"))
      (node (ref "E13") (pin "2") (pinfunction "B_2") (pintype "input"))
    )
    (net (code "30") (name "BMB11") (class "Default")
      (node (ref "D35L1") (pin "TT") (pinfunction "38_TT") (pintype "bidirectional"))
      (node (ref "D35L2") (pin "TT") (pinfunction "38_TT") (pintype "bidirectional"))
      (node (ref "E11") (pin "1") (pinfunction "A_1") (pintype "input"))
      (node (ref "E12") (pin "1") (pinfunction "A_1") (pintype "input"))
      (node (ref "E13") (pin "1") (pinfunction "A_1") (pintype "input"))
    )
    (net (code "31") (name "BTS1") (class "Default")
      (node (ref "D36L1") (pin "NN") (pinfunction "34_NN") (pintype "bidirectional"))
      (node (ref "D36L2") (pin "NN") (pinfunction "34_NN") (pintype "bidirectional"))
      (node (ref "E18") (pin "11") (pinfunction "CLK_11") (pintype "input"))
      (node (ref "E19") (pin "11") (pinfunction "CLK_11") (pintype "input"))
      (node (ref "E26") (pin "11") (pinfunction "CLK_11") (pintype "input"))
      (node (ref "LASTDEV") (pin "3") (pinfunction "3_3") (pintype "passive"))
    )
    (net (code "32") (name "BTS3") (class "Default")
      (node (ref "D36L1") (pin "JJ") (pinfunction "30_JJ") (pintype "bidirectional"))
      (node (ref "D36L2") (pin "JJ") (pinfunction "30_JJ") (pintype "bidirectional"))
      (node (ref "LASTDEV") (pin "4") (pinfunction "4_4") (pintype "passive"))
    )
    (net (code "33") (name "CLK_BUF") (class "Default")
      (node (ref "E21") (pin "10") (pinfunction "CLK_10") (pintype "input"))
      (node (ref "E22") (pin "10") (pinfunction "CLK_10") (pintype "input"))
      (node (ref "E23") (pin "10") (pinfunction "CLK_10") (pintype "input"))
      (node (ref "E4") (pin "2") (pinfunction "CLK_2") (pintype "input"))
      (node (ref "E5") (pin "6") (pinfunction "O_6") (pintype "output"))
    )
    (net (code "34") (name "DONE") (class "Default")
      (node (ref "E18") (pin "3") (pinfunction "CLK_3") (pintype "input"))
      (node (ref "E20") (pin "13") (pinfunction "I1_13") (pintype "input"))
      (node (ref "E25") (pin "3") (pinfunction "I_3") (pintype "input"))
      (node (ref "E31") (pin "4") (pinfunction "I2_4") (pintype "input"))
      (node (ref "E32") (pin "11") (pinfunction "I2_11") (pintype "input"))
      (node (ref "E36") (pin "10") (pinfunction "O_10") (pintype "output"))
    )
    (net (code "35") (name "DONE_FF") (class "Default")
      (node (ref "E18") (pin "9") (pinfunction "Q_9") (pintype "output"))
      (node (ref "IC10") (pin "6") (pinfunction "I0_6") (pintype "input"))
    )
    (net (code "36") (name "ERROR") (class "Default")
      (node (ref "E26") (pin "3") (pinfunction "CLK_3") (pintype "input"))
      (node (ref "E36") (pin "1") (pinfunction "O_1") (pintype "output"))
    )
    (net (code "37") (name "GND") (class "Default")
      (node (ref "C1") (pin "2") (pinfunction "2_2") (pintype "passive"))
      (node (ref "C10") (pin "2") (pinfunction "2_2") (pintype "passive"))
      (node (ref "C11") (pin "2") (pinfunction "2_2") (pintype "passive"))
      (node (ref "C12") (pin "2") (pinfunction "2_2") (pintype "passive"))
      (node (ref "C13") (pin "2") (pinfunction "2_2") (pintype "passive"))
      (node (ref "C14") (pin "2") (pinfunction "2_2") (pintype "passive"))
      (node (ref "C15") (pin "2") (pinfunction "2_2") (pintype "passive"))
      (node (ref "C16") (pin "2") (pinfunction "2_2") (pintype "passive"))
      (node (ref "C17") (pin "2") (pinfunction "2_2") (pintype "passive"))
      (node (ref "C18") (pin "2") (pinfunction "2_2") (pintype "passive"))
      (node (ref "C19") (pin "2") (pinfunction "2_2") (pintype "passive"))
      (node (ref "C2") (pin "2") (pinfunction "2_2") (pintype "passive"))
      (node (ref "C20") (pin "2") (pinfunction "2_2") (pintype "passive"))
      (node (ref "C21") (pin "2") (pinfunction "2_2") (pintype "passive"))
      (node (ref "C22") (pin "2") (pinfunction "2_2") (pintype "passive"))
      (node (ref "C23") (pin "2") (pinfunction "2_2") (pintype "passive"))
      (node (ref "C24") (pin "2") (pinfunction "2_2") (pintype "passive"))
      (node (ref "C25") (pin "2") (pinfunction "2_2") (pintype "passive"))
      (node (ref "C26") (pin "2") (pinfunction "2_2") (pintype "passive"))
      (node (ref "C27") (pin "2") (pinfunction "2_2") (pintype "passive"))
      (node (ref "C28") (pin "2") (pinfunction "2_2") (pintype "passive"))
      (node (ref "C29") (pin "2") (pinfunction "2_2") (pintype "passive"))
      (node (ref "C3") (pin "2") (pinfunction "2_2") (pintype "passive"))
      (node (ref "C30") (pin "2") (pinfunction "2_2") (pintype "passive"))
      (node (ref "C31") (pin "2") (pinfunction "2_2") (pintype "passive"))
      (node (ref "C32") (pin "2") (pinfunction "2_2") (pintype "passive"))
      (node (ref "C33") (pin "2") (pinfunction "2_2") (pintype "passive"))
      (node (ref "C34") (pin "2") (pinfunction "2_2") (pintype "passive"))
      (node (ref "C35") (pin "2") (pinfunction "2_2") (pintype "passive"))
      (node (ref "C36") (pin "2") (pinfunction "2_2") (pintype "passive"))
      (node (ref "C37") (pin "2") (pinfunction "2_2") (pintype "passive"))
      (node (ref "C38") (pin "2") (pinfunction "2_2") (pintype "passive"))
      (node (ref "C39") (pin "2") (pinfunction "2_2") (pintype "passive"))
      (node (ref "C4") (pin "2") (pinfunction "2_2") (pintype "passive"))
      (node (ref "C40") (pin "-") (pinfunction "-_-") (pintype "passive"))
      (node (ref "C5") (pin "2") (pinfunction "2_2") (pintype "passive"))
      (node (ref "C6") (pin "2") (pinfunction "2_2") (pintype "passive"))
      (node (ref "C7") (pin "2") (pinfunction "2_2") (pintype "passive"))
      (node (ref "C8") (pin "2") (pinfunction "2_2") (pintype "passive"))
      (node (ref "C9") (pin "2") (pinfunction "2_2") (pintype "passive"))
      (node (ref "D34L1") (pin "A") (pinfunction "1_A") (pintype "bidirectional"))
      (node (ref "D34L1") (pin "AA") (pinfunction "23_AA") (pintype "bidirectional"))
      (node (ref "D34L1") (pin "C") (pinfunction "3_C") (pintype "bidirectional"))
      (node (ref "D34L1") (pin "CC") (pinfunction "25_CC") (pintype "bidirectional"))
      (node (ref "D34L1") (pin "E") (pinfunction "5_E") (pintype "bidirectional"))
      (node (ref "D34L1") (pin "EE") (pinfunction "27_EE") (pintype "bidirectional"))
      (node (ref "D34L1") (pin "H") (pinfunction "7_H") (pintype "bidirectional"))
      (node (ref "D34L1") (pin "HH") (pinfunction "29_HH") (pintype "bidirectional"))
      (node (ref "D34L1") (pin "K") (pinfunction "9_K") (pintype "bidirectional"))
      (node (ref "D34L1") (pin "KK") (pinfunction "31_KK") (pintype "bidirectional"))
      (node (ref "D34L1") (pin "M") (pinfunction "11_M") (pintype "bidirectional"))
      (node (ref "D34L1") (pin "MM") (pinfunction "33_MM") (pintype "bidirectional"))
      (node (ref "D34L1") (pin "P") (pinfunction "13_P") (pintype "bidirectional"))
      (node (ref "D34L1") (pin "PP") (pinfunction "35_PP") (pintype "bidirectional"))
      (node (ref "D34L1") (pin "S") (pinfunction "15_S") (pintype "bidirectional"))
      (node (ref "D34L1") (pin "SS") (pinfunction "37_SS") (pintype "bidirectional"))
      (node (ref "D34L1") (pin "U") (pinfunction "17_U") (pintype "bidirectional"))
      (node (ref "D34L1") (pin "UU") (pinfunction "39_UU") (pintype "bidirectional"))
      (node (ref "D34L1") (pin "W") (pinfunction "19_W") (pintype "bidirectional"))
      (node (ref "D34L1") (pin "Y") (pinfunction "21_Y") (pintype "bidirectional"))
      (node (ref "D34L2") (pin "A") (pinfunction "1_A") (pintype "bidirectional"))
      (node (ref "D34L2") (pin "AA") (pinfunction "23_AA") (pintype "bidirectional"))
      (node (ref "D34L2") (pin "C") (pinfunction "3_C") (pintype "bidirectional"))
      (node (ref "D34L2") (pin "CC") (pinfunction "25_CC") (pintype "bidirectional"))
      (node (ref "D34L2") (pin "E") (pinfunction "5_E") (pintype "bidirectional"))
      (node (ref "D34L2") (pin "EE") (pinfunction "27_EE") (pintype "bidirectional"))
      (node (ref "D34L2") (pin "H") (pinfunction "7_H") (pintype "bidirectional"))
      (node (ref "D34L2") (pin "HH") (pinfunction "29_HH") (pintype "bidirectional"))
      (node (ref "D34L2") (pin "K") (pinfunction "9_K") (pintype "bidirectional"))
      (node (ref "D34L2") (pin "KK") (pinfunction "31_KK") (pintype "bidirectional"))
      (node (ref "D34L2") (pin "M") (pinfunction "11_M") (pintype "bidirectional"))
      (node (ref "D34L2") (pin "MM") (pinfunction "33_MM") (pintype "bidirectional"))
      (node (ref "D34L2") (pin "P") (pinfunction "13_P") (pintype "bidirectional"))
      (node (ref "D34L2") (pin "PP") (pinfunction "35_PP") (pintype "bidirectional"))
      (node (ref "D34L2") (pin "S") (pinfunction "15_S") (pintype "bidirectional"))
      (node (ref "D34L2") (pin "SS") (pinfunction "37_SS") (pintype "bidirectional"))
      (node (ref "D34L2") (pin "U") (pinfunction "17_U") (pintype "bidirectional"))
      (node (ref "D34L2") (pin "UU") (pinfunction "39_UU") (pintype "bidirectional"))
      (node (ref "D34L2") (pin "W") (pinfunction "19_W") (pintype "bidirectional"))
      (node (ref "D34L2") (pin "Y") (pinfunction "21_Y") (pintype "bidirectional"))
      (node (ref "D35L1") (pin "A") (pinfunction "1_A") (pintype "bidirectional"))
      (node (ref "D35L1") (pin "AA") (pinfunction "23_AA") (pintype "bidirectional"))
      (node (ref "D35L1") (pin "C") (pinfunction "3_C") (pintype "bidirectional"))
      (node (ref "D35L1") (pin "CC") (pinfunction "25_CC") (pintype "bidirectional"))
      (node (ref "D35L1") (pin "E") (pinfunction "5_E") (pintype "bidirectional"))
      (node (ref "D35L1") (pin "EE") (pinfunction "27_EE") (pintype "bidirectional"))
      (node (ref "D35L1") (pin "H") (pinfunction "7_H") (pintype "bidirectional"))
      (node (ref "D35L1") (pin "HH") (pinfunction "29_HH") (pintype "bidirectional"))
      (node (ref "D35L1") (pin "K") (pinfunction "9_K") (pintype "bidirectional"))
      (node (ref "D35L1") (pin "KK") (pinfunction "31_KK") (pintype "bidirectional"))
      (node (ref "D35L1") (pin "M") (pinfunction "11_M") (pintype "bidirectional"))
      (node (ref "D35L1") (pin "MM") (pinfunction "33_MM") (pintype "bidirectional"))
      (node (ref "D35L1") (pin "P") (pinfunction "13_P") (pintype "bidirectional"))
      (node (ref "D35L1") (pin "PP") (pinfunction "35_PP") (pintype "bidirectional"))
      (node (ref "D35L1") (pin "S") (pinfunction "15_S") (pintype "bidirectional"))
      (node (ref "D35L1") (pin "SS") (pinfunction "37_SS") (pintype "bidirectional"))
      (node (ref "D35L1") (pin "U") (pinfunction "17_U") (pintype "bidirectional"))
      (node (ref "D35L1") (pin "UU") (pinfunction "39_UU") (pintype "bidirectional"))
      (node (ref "D35L1") (pin "W") (pinfunction "19_W") (pintype "bidirectional"))
      (node (ref "D35L1") (pin "Y") (pinfunction "21_Y") (pintype "bidirectional"))
      (node (ref "D35L2") (pin "A") (pinfunction "1_A") (pintype "bidirectional"))
      (node (ref "D35L2") (pin "AA") (pinfunction "23_AA") (pintype "bidirectional"))
      (node (ref "D35L2") (pin "C") (pinfunction "3_C") (pintype "bidirectional"))
      (node (ref "D35L2") (pin "CC") (pinfunction "25_CC") (pintype "bidirectional"))
      (node (ref "D35L2") (pin "E") (pinfunction "5_E") (pintype "bidirectional"))
      (node (ref "D35L2") (pin "EE") (pinfunction "27_EE") (pintype "bidirectional"))
      (node (ref "D35L2") (pin "H") (pinfunction "7_H") (pintype "bidirectional"))
      (node (ref "D35L2") (pin "HH") (pinfunction "29_HH") (pintype "bidirectional"))
      (node (ref "D35L2") (pin "K") (pinfunction "9_K") (pintype "bidirectional"))
      (node (ref "D35L2") (pin "KK") (pinfunction "31_KK") (pintype "bidirectional"))
      (node (ref "D35L2") (pin "M") (pinfunction "11_M") (pintype "bidirectional"))
      (node (ref "D35L2") (pin "MM") (pinfunction "33_MM") (pintype "bidirectional"))
      (node (ref "D35L2") (pin "P") (pinfunction "13_P") (pintype "bidirectional"))
      (node (ref "D35L2") (pin "PP") (pinfunction "35_PP") (pintype "bidirectional"))
      (node (ref "D35L2") (pin "S") (pinfunction "15_S") (pintype "bidirectional"))
      (node (ref "D35L2") (pin "SS") (pinfunction "37_SS") (pintype "bidirectional"))
      (node (ref "D35L2") (pin "U") (pinfunction "17_U") (pintype "bidirectional"))
      (node (ref "D35L2") (pin "UU") (pinfunction "39_UU") (pintype "bidirectional"))
      (node (ref "D35L2") (pin "W") (pinfunction "19_W") (pintype "bidirectional"))
      (node (ref "D35L2") (pin "Y") (pinfunction "21_Y") (pintype "bidirectional"))
      (node (ref "D36L1") (pin "A") (pinfunction "1_A") (pintype "bidirectional"))
      (node (ref "D36L1") (pin "AA") (pinfunction "23_AA") (pintype "bidirectional"))
      (node (ref "D36L1") (pin "C") (pinfunction "3_C") (pintype "bidirectional"))
      (node (ref "D36L1") (pin "CC") (pinfunction "25_CC") (pintype "bidirectional"))
      (node (ref "D36L1") (pin "E") (pinfunction "5_E") (pintype "bidirectional"))
      (node (ref "D36L1") (pin "EE") (pinfunction "27_EE") (pintype "bidirectional"))
      (node (ref "D36L1") (pin "H") (pinfunction "7_H") (pintype "bidirectional"))
      (node (ref "D36L1") (pin "HH") (pinfunction "29_HH") (pintype "bidirectional"))
      (node (ref "D36L1") (pin "K") (pinfunction "9_K") (pintype "bidirectional"))
      (node (ref "D36L1") (pin "KK") (pinfunction "31_KK") (pintype "bidirectional"))
      (node (ref "D36L1") (pin "M") (pinfunction "11_M") (pintype "bidirectional"))
      (node (ref "D36L1") (pin "MM") (pinfunction "33_MM") (pintype "bidirectional"))
      (node (ref "D36L1") (pin "P") (pinfunction "13_P") (pintype "bidirectional"))
      (node (ref "D36L1") (pin "PP") (pinfunction "35_PP") (pintype "bidirectional"))
      (node (ref "D36L1") (pin "S") (pinfunction "15_S") (pintype "bidirectional"))
      (node (ref "D36L1") (pin "SS") (pinfunction "37_SS") (pintype "bidirectional"))
      (node (ref "D36L1") (pin "U") (pinfunction "17_U") (pintype "bidirectional"))
      (node (ref "D36L1") (pin "UU") (pinfunction "39_UU") (pintype "bidirectional"))
      (node (ref "D36L1") (pin "W") (pinfunction "19_W") (pintype "bidirectional"))
      (node (ref "D36L1") (pin "Y") (pinfunction "21_Y") (pintype "bidirectional"))
      (node (ref "D36L2") (pin "A") (pinfunction "1_A") (pintype "bidirectional"))
      (node (ref "D36L2") (pin "AA") (pinfunction "23_AA") (pintype "bidirectional"))
      (node (ref "D36L2") (pin "C") (pinfunction "3_C") (pintype "bidirectional"))
      (node (ref "D36L2") (pin "CC") (pinfunction "25_CC") (pintype "bidirectional"))
      (node (ref "D36L2") (pin "E") (pinfunction "5_E") (pintype "bidirectional"))
      (node (ref "D36L2") (pin "EE") (pinfunction "27_EE") (pintype "bidirectional"))
      (node (ref "D36L2") (pin "H") (pinfunction "7_H") (pintype "bidirectional"))
      (node (ref "D36L2") (pin "HH") (pinfunction "29_HH") (pintype "bidirectional"))
      (node (ref "D36L2") (pin "K") (pinfunction "9_K") (pintype "bidirectional"))
      (node (ref "D36L2") (pin "KK") (pinfunction "31_KK") (pintype "bidirectional"))
      (node (ref "D36L2") (pin "M") (pinfunction "11_M") (pintype "bidirectional"))
      (node (ref "D36L2") (pin "MM") (pinfunction "33_MM") (pintype "bidirectional"))
      (node (ref "D36L2") (pin "P") (pinfunction "13_P") (pintype "bidirectional"))
      (node (ref "D36L2") (pin "PP") (pinfunction "35_PP") (pintype "bidirectional"))
      (node (ref "D36L2") (pin "S") (pinfunction "15_S") (pintype "bidirectional"))
      (node (ref "D36L2") (pin "SS") (pinfunction "37_SS") (pintype "bidirectional"))
      (node (ref "D36L2") (pin "U") (pinfunction "17_U") (pintype "bidirectional"))
      (node (ref "D36L2") (pin "UU") (pinfunction "39_UU") (pintype "bidirectional"))
      (node (ref "D36L2") (pin "W") (pinfunction "19_W") (pintype "bidirectional"))
      (node (ref "D36L2") (pin "Y") (pinfunction "21_Y") (pintype "bidirectional"))
      (node (ref "DRIVE") (pin "A") (pinfunction "1_A") (pintype "bidirectional"))
      (node (ref "DRIVE") (pin "AA") (pinfunction "23_AA") (pintype "bidirectional"))
      (node (ref "DRIVE") (pin "B") (pinfunction "2_B") (pintype "bidirectional"))
      (node (ref "DRIVE") (pin "C") (pinfunction "3_C") (pintype "bidirectional"))
      (node (ref "DRIVE") (pin "CC") (pinfunction "25_CC") (pintype "bidirectional"))
      (node (ref "DRIVE") (pin "DD") (pinfunction "26_DD") (pintype "bidirectional"))
      (node (ref "DRIVE") (pin "E") (pinfunction "5_E") (pintype "bidirectional"))
      (node (ref "DRIVE") (pin "EE") (pinfunction "27_EE") (pintype "bidirectional"))
      (node (ref "DRIVE") (pin "F") (pinfunction "6_F") (pintype "bidirectional"))
      (node (ref "DRIVE") (pin "H") (pinfunction "7_H") (pintype "bidirectional"))
      (node (ref "DRIVE") (pin "HH") (pinfunction "29_HH") (pintype "bidirectional"))
      (node (ref "DRIVE") (pin "JJ") (pinfunction "30_JJ") (pintype "bidirectional"))
      (node (ref "DRIVE") (pin "K") (pinfunction "9_K") (pintype "bidirectional"))
      (node (ref "DRIVE") (pin "KK") (pinfunction "31_KK") (pintype "bidirectional"))
      (node (ref "DRIVE") (pin "L") (pinfunction "10_L") (pintype "bidirectional"))
      (node (ref "DRIVE") (pin "M") (pinfunction "11_M") (pintype "bidirectional"))
      (node (ref "DRIVE") (pin "MM") (pinfunction "33_MM") (pintype "bidirectional"))
      (node (ref "DRIVE") (pin "NN") (pinfunction "34_NN") (pintype "bidirectional"))
      (node (ref "DRIVE") (pin "P") (pinfunction "13_P") (pintype "bidirectional"))
      (node (ref "DRIVE") (pin "PP") (pinfunction "35_PP") (pintype "bidirectional"))
      (node (ref "DRIVE") (pin "R") (pinfunction "14_R") (pintype "bidirectional"))
      (node (ref "DRIVE") (pin "S") (pinfunction "15_S") (pintype "bidirectional"))
      (node (ref "DRIVE") (pin "SS") (pinfunction "37_SS") (pintype "bidirectional"))
      (node (ref "DRIVE") (pin "TT") (pinfunction "38_TT") (pintype "bidirectional"))
      (node (ref "DRIVE") (pin "U") (pinfunction "17_U") (pintype "bidirectional"))
      (node (ref "DRIVE") (pin "UU") (pinfunction "39_UU") (pintype "bidirectional"))
      (node (ref "DRIVE") (pin "V") (pinfunction "18_V") (pintype "bidirectional"))
      (node (ref "DRIVE") (pin "VV") (pinfunction "40_VV") (pintype "bidirectional"))
      (node (ref "DRIVE") (pin "W") (pinfunction "19_W") (pintype "bidirectional"))
      (node (ref "DRIVE") (pin "Y") (pinfunction "21_Y") (pintype "bidirectional"))
      (node (ref "DRIVE") (pin "Z") (pinfunction "22_Z") (pintype "bidirectional"))
      (node (ref "E11") (pin "5") (pinfunction "G2B_5") (pintype "input"))
      (node (ref "E12") (pin "5") (pinfunction "G2B_5") (pintype "input"))
      (node (ref "E13") (pin "5") (pinfunction "G2B_5") (pintype "input"))
      (node (ref "E2") (pin "2") (pinfunction "D_2") (pintype "input"))
      (node (ref "E4") (pin "6") (pinfunction "D_6") (pintype "input"))
      (node (ref "LASTDEV") (pin "1") (pinfunction "1_1") (pintype "passive"))
      (node (ref "R10") (pin "1") (pinfunction "1_1") (pintype "passive"))
      (node (ref "R11") (pin "1") (pinfunction "1_1") (pintype "passive"))
      (node (ref "R12") (pin "1") (pinfunction "1_1") (pintype "passive"))
      (node (ref "R13") (pin "1") (pinfunction "1_1") (pintype "passive"))
      (node (ref "R14") (pin "1") (pinfunction "1_1") (pintype "passive"))
      (node (ref "R15") (pin "1") (pinfunction "1_1") (pintype "passive"))
      (node (ref "R16") (pin "1") (pinfunction "1_1") (pintype "passive"))
      (node (ref "R17") (pin "1") (pinfunction "1_1") (pintype "passive"))
      (node (ref "SL1") (pin "2") (pinfunction "S_2") (pintype "passive"))
      (node (ref "SL1") (pin "3") (pinfunction "S_3") (pintype "passive"))
    )
    (net (code "38") (name "INIT") (class "Default")
      (node (ref "E1") (pin "8") (pinfunction "O_8") (pintype "output"))
      (node (ref "E15") (pin "4") (pinfunction "I0_4") (pintype "input"))
      (node (ref "E15") (pin "5") (pinfunction "I1_5") (pintype "input"))
      (node (ref "E36") (pin "12") (pinfunction "I1_12") (pintype "input"))
      (node (ref "IC8") (pin "6") (pinfunction "I0_6") (pintype "input"))
      (node (ref "IC8") (pin "7") (pinfunction "I1_7") (pintype "input"))
    )
    (net (code "39") (name "MAINT") (class "Default")
      (node (ref "E16") (pin "9") (pinfunction "Q_9") (pintype "output"))
      (node (ref "E32") (pin "9") (pinfunction "I0_9") (pintype "input"))
      (node (ref "E35") (pin "3") (pinfunction "I1_3") (pintype "input"))
      (node (ref "E35") (pin "6") (pinfunction "I1_6") (pintype "input"))
      (node (ref "E35") (pin "9") (pinfunction "I1_9") (pintype "input"))
      (node (ref "E36") (pin "2") (pinfunction "I0_2") (pintype "input"))
      (node (ref "E36") (pin "6") (pinfunction "I1_6") (pintype "input"))
      (node (ref "E36") (pin "9") (pinfunction "I1_9") (pintype "input"))
    )
    (net (code "40") (name "MSB8") (class "Default")
      (node (ref "E21") (pin "12") (pinfunction "QD_12") (pintype "output"))
      (node (ref "E23") (pin "2") (pinfunction "J_2") (pintype "input"))
      (node (ref "E23") (pin "3") (pinfunction "K_3") (pintype "input"))
      (node (ref "E8") (pin "5") (pinfunction "I2_5") (pintype "input"))
      (node (ref "IC1") (pin "6") (pinfunction "I0_6") (pintype "input"))
    )
    (net (code "41") (name "MSB12") (class "Default")
      (node (ref "E23") (pin "12") (pinfunction "QD_12") (pintype "output"))
      (node (ref "E8") (pin "2") (pinfunction "I1_2") (pintype "input"))
      (node (ref "IC6") (pin "1") (pinfunction "I0_1") (pintype "input"))
    )
    (net (code "42") (name "Net-(70-P)") (class "Default")
      (node (ref "70") (pin "1") (pinfunction "P_1") (pintype "passive"))
      (node (ref "E14") (pin "15") (pinfunction "Y0_15") (pintype "output"))
    )
    (net (code "43") (name "Net-(71-P)") (class "Default")
      (node (ref "71") (pin "1") (pinfunction "P_1") (pintype "passive"))
      (node (ref "E14") (pin "14") (pinfunction "Y1_14") (pintype "output"))
    )
    (net (code "44") (name "Net-(72-P)") (class "Default")
      (node (ref "72") (pin "1") (pinfunction "P_1") (pintype "passive"))
      (node (ref "E14") (pin "13") (pinfunction "Y2_13") (pintype "output"))
    )
    (net (code "45") (name "Net-(73-P)") (class "Default")
      (node (ref "73") (pin "1") (pinfunction "P_1") (pintype "passive"))
      (node (ref "E14") (pin "12") (pinfunction "Y3_12") (pintype "output"))
    )
    (net (code "46") (name "Net-(74-P)") (class "Default")
      (node (ref "74") (pin "1") (pinfunction "P_1") (pintype "passive"))
      (node (ref "E14") (pin "11") (pinfunction "Y4_11") (pintype "output"))
    )
    (net (code "47") (name "Net-(75-P)") (class "Default")
      (node (ref "75") (pin "1") (pinfunction "P_1") (pintype "passive"))
      (node (ref "E14") (pin "10") (pinfunction "Y5_10") (pintype "output"))
    )
    (net (code "48") (name "Net-(76-P)") (class "Default")
      (node (ref "76") (pin "1") (pinfunction "P_1") (pintype "passive"))
      (node (ref "E14") (pin "9") (pinfunction "Y6_9") (pintype "output"))
    )
    (net (code "49") (name "Net-(77-P)") (class "Default")
      (node (ref "77") (pin "1") (pinfunction "P_1") (pintype "passive"))
      (node (ref "E14") (pin "7") (pinfunction "Y7_7") (pintype "output"))
    )
    (net (code "50") (name "Net-(E1B-O)") (class "Default")
      (node (ref "E1") (pin "10") (pinfunction "I1_10") (pintype "input"))
      (node (ref "E1") (pin "6") (pinfunction "O_6") (pintype "output"))
      (node (ref "E1") (pin "9") (pinfunction "I0_9") (pintype "input"))
      (node (ref "E2") (pin "1") (pinfunction "CLR_1") (pintype "input"))
    )
    (net (code "51") (name "Net-(E1C-I2)") (class "Default")
      (node (ref "E1") (pin "11") (pinfunction "I2_11") (pintype "input"))
      (node (ref "E2") (pin "6") (pinfunction "~{Q}_6") (pintype "output"))
    )
    (net (code "52") (name "Net-(E4A-A)") (class "Default")
      (node (ref "E4") (pin "10") (pinfunction "ENT_10") (pintype "input"))
      (node (ref "E4") (pin "3") (pinfunction "A_3") (pintype "input"))
      (node (ref "E4") (pin "4") (pinfunction "B_4") (pintype "input"))
      (node (ref "E4") (pin "7") (pinfunction "ENP_7") (pintype "input"))
      (node (ref "R19") (pin "2") (pinfunction "2_2") (pintype "passive"))
    )
    (net (code "53") (name "Net-(E4A-C)") (class "Default")
      (node (ref "E4") (pin "5") (pinfunction "C_5") (pintype "input"))
      (node (ref "E5") (pin "3") (pinfunction "O_3") (pintype "output"))
    )
    (net (code "54") (name "Net-(E5A-I0)") (class "Default")
      (node (ref "E5") (pin "1") (pinfunction "I0_1") (pintype "input"))
      (node (ref "E5") (pin "11") (pinfunction "O_11") (pintype "output"))
    )
    (net (code "55") (name "Net-(E6A-I1)") (class "Default")
      (node (ref "E6") (pin "2") (pinfunction "I1_2") (pintype "input"))
      (node (ref "E6") (pin "8") (pinfunction "O_8") (pintype "output"))
    )
    (net (code "56") (name "Net-(E6A-O)") (class "Default")
      (node (ref "E6") (pin "3") (pinfunction "O_3") (pintype "output"))
      (node (ref "IC10") (pin "1") (pinfunction "I0_1") (pintype "input"))
      (node (ref "IC10") (pin "2") (pinfunction "I1_2") (pintype "input"))
    )
    (net (code "57") (name "Net-(E6B-O)") (class "Default")
      (node (ref "E6") (pin "10") (pinfunction "I1_10") (pintype "input"))
      (node (ref "E6") (pin "6") (pinfunction "O_6") (pintype "output"))
      (node (ref "E6") (pin "9") (pinfunction "I0_9") (pintype "input"))
    )
    (net (code "58") (name "Net-(E8A-O)") (class "Default")
      (node (ref "E8") (pin "11") (pinfunction "I2_11") (pintype "input"))
      (node (ref "E8") (pin "12") (pinfunction "O_12") (pintype "output"))
    )
    (net (code "59") (name "Net-(E8B-O)") (class "Default")
      (node (ref "E8") (pin "6") (pinfunction "O_6") (pintype "output"))
      (node (ref "E8") (pin "9") (pinfunction "I0_9") (pintype "input"))
    )
    (net (code "60") (name "Net-(E10A-I0)") (class "Default")
      (node (ref "E10") (pin "1") (pinfunction "I0_1") (pintype "input"))
      (node (ref "E10") (pin "6") (pinfunction "O_6") (pintype "output"))
    )
    (net (code "61") (name "Net-(E10A-O)") (class "Default")
      (node (ref "E10") (pin "10") (pinfunction "I1_10") (pintype "input"))
      (node (ref "E10") (pin "11") (pinfunction "I2_11") (pintype "input"))
      (node (ref "E10") (pin "12") (pinfunction "O_12") (pintype "output"))
    )
    (net (code "62") (name "Net-(E10C-O)") (class "Default")
      (node (ref "E10") (pin "8") (pinfunction "O_8") (pintype "output"))
      (node (ref "IC7") (pin "1") (pinfunction "I0_1") (pintype "input"))
      (node (ref "IC7") (pin "2") (pinfunction "I1_2") (pintype "input"))
    )
    (net (code "63") (name "Net-(E14A-G2A)") (class "Default")
      (node (ref "E1") (pin "12") (pinfunction "O_12") (pintype "output"))
      (node (ref "E14") (pin "4") (pinfunction "G2A_4") (pintype "input"))
      (node (ref "E14") (pin "5") (pinfunction "G2B_5") (pintype "input"))
    )
    (net (code "64") (name "Net-(E15A-O)") (class "Default")
      (node (ref "E15") (pin "3") (pinfunction "O_3") (pintype "output"))
      (node (ref "E8") (pin "13") (pinfunction "I2_13") (pintype "input"))
      (node (ref "E8") (pin "3") (pinfunction "I0_3") (pintype "input"))
    )
    (net (code "65") (name "Net-(E15C-I0)") (class "Default")
      (node (ref "E15") (pin "9") (pinfunction "I0_9") (pintype "input"))
      (node (ref "E20") (pin "11") (pinfunction "O_11") (pintype "output"))
      (node (ref "E24") (pin "10") (pinfunction "I1_10") (pintype "input"))
    )
    (net (code "66") (name "Net-(E15C-O)") (class "Default")
      (node (ref "E15") (pin "8") (pinfunction "O_8") (pintype "output"))
      (node (ref "E24") (pin "12") (pinfunction "I0_12") (pintype "input"))
    )
    (net (code "67") (name "Net-(E15D-O)") (class "Default")
      (node (ref "E15") (pin "11") (pinfunction "O_11") (pintype "output"))
      (node (ref "E8") (pin "10") (pinfunction "I1_10") (pintype "input"))
    )
    (net (code "68") (name "Net-(E17B-CLR)") (class "Default")
      (node (ref "E17") (pin "8") (pinfunction "CLR_8") (pintype "input"))
      (node (ref "E36") (pin "13") (pinfunction "O_13") (pintype "output"))
    )
    (net (code "69") (name "Net-(E17B-J)") (class "Default")
      (node (ref "E17") (pin "12") (pinfunction "K_12") (pintype "input"))
      (node (ref "E17") (pin "9") (pinfunction "J_9") (pintype "input"))
      (node (ref "E8") (pin "8") (pinfunction "O_8") (pintype "output"))
      (node (ref "IC7") (pin "7") (pinfunction "I1_7") (pintype "input"))
    )
    (net (code "70") (name "Net-(E18A-Q)") (class "Default")
      (node (ref "E18") (pin "12") (pinfunction "D_12") (pintype "input"))
      (node (ref "E18") (pin "5") (pinfunction "Q_5") (pintype "output"))
    )
    (net (code "71") (name "Net-(E18B-~{Q})") (class "Default")
      (node (ref "E18") (pin "8") (pinfunction "~{Q}_8") (pintype "output"))
      (node (ref "E20") (pin "10") (pinfunction "I1_10") (pintype "input"))
    )
    (net (code "72") (name "Net-(E19A-Q)") (class "Default")
      (node (ref "E19") (pin "12") (pinfunction "D_12") (pintype "input"))
      (node (ref "E19") (pin "5") (pinfunction "Q_5") (pintype "output"))
    )
    (net (code "73") (name "Net-(E19B-~{Q})") (class "Default")
      (node (ref "E19") (pin "8") (pinfunction "~{Q}_8") (pintype "output"))
      (node (ref "E20") (pin "2") (pinfunction "I1_2") (pintype "input"))
    )
    (net (code "74") (name "Net-(E20B-I1)") (class "Default")
      (node (ref "E20") (pin "5") (pinfunction "I1_5") (pintype "input"))
      (node (ref "E26") (pin "8") (pinfunction "~{Q}_8") (pintype "output"))
    )
    (net (code "75") (name "Net-(E21A-J)") (class "Default")
      (node (ref "E21") (pin "2") (pinfunction "J_2") (pintype "input"))
      (node (ref "E21") (pin "3") (pinfunction "K_3") (pintype "input"))
      (node (ref "E22") (pin "12") (pinfunction "QD_12") (pintype "output"))
      (node (ref "IC4") (pin "6") (pinfunction "I0_6") (pintype "input"))
    )
    (net (code "76") (name "Net-(E21A-QA)") (class "Default")
      (node (ref "E21") (pin "15") (pinfunction "QA_15") (pintype "output"))
      (node (ref "IC3") (pin "6") (pinfunction "I0_6") (pintype "input"))
    )
    (net (code "77") (name "Net-(E21A-QB)") (class "Default")
      (node (ref "E21") (pin "14") (pinfunction "QB_14") (pintype "output"))
      (node (ref "IC3") (pin "1") (pinfunction "I0_1") (pintype "input"))
    )
    (net (code "78") (name "Net-(E21A-QC)") (class "Default")
      (node (ref "E21") (pin "13") (pinfunction "QC_13") (pintype "output"))
      (node (ref "IC4") (pin "1") (pinfunction "I0_1") (pintype "input"))
    )
    (net (code "79") (name "Net-(E22A-QA)") (class "Default")
      (node (ref "E22") (pin "15") (pinfunction "QA_15") (pintype "output"))
      (node (ref "IC2") (pin "1") (pinfunction "I0_1") (pintype "input"))
    )
    (net (code "80") (name "Net-(E22A-QB)") (class "Default")
      (node (ref "E22") (pin "14") (pinfunction "QB_14") (pintype "output"))
      (node (ref "IC5") (pin "6") (pinfunction "I0_6") (pintype "input"))
    )
    (net (code "81") (name "Net-(E22A-QC)") (class "Default")
      (node (ref "E22") (pin "13") (pinfunction "QC_13") (pintype "output"))
      (node (ref "IC5") (pin "1") (pinfunction "I0_1") (pintype "input"))
    )
    (net (code "82") (name "Net-(E23A-QA)") (class "Default")
      (node (ref "E23") (pin "15") (pinfunction "QA_15") (pintype "output"))
      (node (ref "IC2") (pin "6") (pinfunction "I0_6") (pintype "input"))
    )
    (net (code "83") (name "Net-(E23A-QB)") (class "Default")
      (node (ref "E23") (pin "14") (pinfunction "QB_14") (pintype "output"))
      (node (ref "IC1") (pin "1") (pinfunction "I0_1") (pintype "input"))
    )
    (net (code "84") (name "Net-(E23A-QC)") (class "Default")
      (node (ref "E23") (pin "13") (pinfunction "QC_13") (pintype "output"))
      (node (ref "IC6") (pin "6") (pinfunction "I0_6") (pintype "input"))
    )
    (net (code "85") (name "Net-(E24A-I1)") (class "Default")
      (node (ref "E24") (pin "2") (pinfunction "I1_2") (pintype "input"))
      (node (ref "E35") (pin "13") (pinfunction "O_13") (pintype "output"))
      (node (ref "IC1") (pin "7") (pinfunction "I1_7") (pintype "input"))
      (node (ref "IC2") (pin "2") (pinfunction "I1_2") (pintype "input"))
      (node (ref "IC3") (pin "2") (pinfunction "I1_2") (pintype "input"))
      (node (ref "IC3") (pin "7") (pinfunction "I1_7") (pintype "input"))
      (node (ref "IC4") (pin "2") (pinfunction "I1_2") (pintype "input"))
      (node (ref "IC4") (pin "7") (pinfunction "I1_7") (pintype "input"))
      (node (ref "IC5") (pin "2") (pinfunction "I1_2") (pintype "input"))
      (node (ref "IC5") (pin "7") (pinfunction "I1_7") (pintype "input"))
    )
    (net (code "86") (name "Net-(E24A-O)") (class "Default")
      (node (ref "E24") (pin "3") (pinfunction "O_3") (pintype "output"))
      (node (ref "IC1") (pin "2") (pinfunction "I1_2") (pintype "input"))
      (node (ref "IC2") (pin "7") (pinfunction "I1_7") (pintype "input"))
      (node (ref "IC6") (pin "2") (pinfunction "I1_2") (pintype "input"))
      (node (ref "IC6") (pin "7") (pinfunction "I1_7") (pintype "input"))
    )
    (net (code "87") (name "Net-(E24B-O)") (class "Default")
      (node (ref "E24") (pin "6") (pinfunction "O_6") (pintype "output"))
      (node (ref "E32") (pin "1") (pinfunction "I0_1") (pintype "input"))
    )
    (net (code "88") (name "Net-(E24C-O)") (class "Default")
      (node (ref "E24") (pin "8") (pinfunction "O_8") (pintype "output"))
      (node (ref "E30") (pin "13") (pinfunction "CLR_13") (pintype "input"))
    )
    (net (code "89") (name "Net-(E25C-O)") (class "Default")
      (node (ref "E25") (pin "6") (pinfunction "O_6") (pintype "output"))
      (node (ref "E31") (pin "1") (pinfunction "I0_1") (pintype "input"))
      (node (ref "E31") (pin "2") (pinfunction "I1_2") (pintype "input"))
    )
    (net (code "90") (name "Net-(E25D-O)") (class "Default")
      (node (ref "E25") (pin "8") (pinfunction "O_8") (pintype "output"))
      (node (ref "E31") (pin "13") (pinfunction "I3_13") (pintype "input"))
    )
    (net (code "91") (name "Net-(E25E-O)") (class "Default")
      (node (ref "E2") (pin "12") (pinfunction "D_12") (pintype "input"))
      (node (ref "E25") (pin "10") (pinfunction "O_10") (pintype "output"))
    )
    (net (code "92") (name "Net-(E25F-O)") (class "Default")
      (node (ref "E2") (pin "11") (pinfunction "CLK_11") (pintype "input"))
      (node (ref "E25") (pin "12") (pinfunction "O_12") (pintype "output"))
    )
    (net (code "93") (name "Net-(E26A-Q)") (class "Default")
      (node (ref "E26") (pin "12") (pinfunction "D_12") (pintype "input"))
      (node (ref "E26") (pin "5") (pinfunction "Q_5") (pintype "output"))
    )
    (net (code "94") (name "Net-(E30A-Q)") (class "Default")
      (node (ref "E30") (pin "5") (pinfunction "Q_5") (pintype "output"))
      (node (ref "IC10") (pin "7") (pinfunction "I1_7") (pintype "input"))
    )
    (net (code "95") (name "Net-(E30B-CLK)") (class "Default")
      (node (ref "E30") (pin "11") (pinfunction "CLK_11") (pintype "input"))
      (node (ref "IC9") (pin "3") (pinfunction "O_3") (pintype "open_collector"))
      (node (ref "R18") (pin "1") (pinfunction "1_1") (pintype "passive"))
    )
    (net (code "96") (name "Net-(E31A-O)") (class "Default")
      (node (ref "E31") (pin "6") (pinfunction "O_6") (pintype "output"))
      (node (ref "IC9") (pin "1") (pinfunction "I0_1") (pintype "input"))
    )
    (net (code "97") (name "Net-(E31B-O)") (class "Default")
      (node (ref "E31") (pin "8") (pinfunction "O_8") (pintype "output"))
      (node (ref "IC9") (pin "2") (pinfunction "I1_2") (pintype "input"))
    )
    (net (code "98") (name "Net-(E32A-O)") (class "Default")
      (node (ref "E32") (pin "12") (pinfunction "O_12") (pintype "output"))
      (node (ref "E32") (pin "4") (pinfunction "I1_4") (pintype "input"))
      (node (ref "E32") (pin "5") (pinfunction "I2_5") (pintype "input"))
    )
    (net (code "99") (name "Net-(E32C-O)") (class "Default")
      (node (ref "E32") (pin "8") (pinfunction "O_8") (pintype "output"))
      (node (ref "E35") (pin "11") (pinfunction "I0_11") (pintype "input"))
    )
    (net (code "100") (name "Net-(PAD10-P)") (class "Default")
      (node (ref "E38") (pin "1") (pinfunction "1_1") (pintype "passive"))
      (node (ref "PAD10") (pin "1") (pinfunction "P_1") (pintype "passive"))
    )
    (net (code "101") (name "Net-(PAD11-P)") (class "Default")
      (node (ref "E38") (pin "2") (pinfunction "2_2") (pintype "passive"))
      (node (ref "PAD11") (pin "1") (pinfunction "P_1") (pintype "passive"))
    )
    (net (code "102") (name "Net-(PAD12-P)") (class "Default")
      (node (ref "E38") (pin "3") (pinfunction "3_3") (pintype "passive"))
      (node (ref "PAD12") (pin "1") (pinfunction "P_1") (pintype "passive"))
    )
    (net (code "103") (name "Net-(PAD13-P)") (class "Default")
      (node (ref "E38") (pin "4") (pinfunction "4_4") (pintype "passive"))
      (node (ref "PAD13") (pin "1") (pinfunction "P_1") (pintype "passive"))
    )
    (net (code "104") (name "Net-(PAD14-P)") (class "Default")
      (node (ref "E38") (pin "5") (pinfunction "5_5") (pintype "passive"))
      (node (ref "PAD14") (pin "1") (pinfunction "P_1") (pintype "passive"))
    )
    (net (code "105") (name "Net-(PAD15-P)") (class "Default")
      (node (ref "E38") (pin "6") (pinfunction "6_6") (pintype "passive"))
      (node (ref "PAD15") (pin "1") (pinfunction "P_1") (pintype "passive"))
    )
    (net (code "106") (name "Net-(PAD16-P)") (class "Default")
      (node (ref "E38") (pin "7") (pinfunction "7_7") (pintype "passive"))
      (node (ref "PAD16") (pin "1") (pinfunction "P_1") (pintype "passive"))
    )
    (net (code "107") (name "Net-(PAD17-P)") (class "Default")
      (node (ref "E38") (pin "8") (pinfunction "8_8") (pintype "passive"))
      (node (ref "PAD17") (pin "1") (pinfunction "P_1") (pintype "passive"))
    )
    (net (code "108") (name "Net-(PAD18-P)") (class "Default")
      (node (ref "E40") (pin "1") (pinfunction "1_1") (pintype "passive"))
      (node (ref "PAD18") (pin "1") (pinfunction "P_1") (pintype "passive"))
    )
    (net (code "109") (name "Net-(PAD19-P)") (class "Default")
      (node (ref "E40") (pin "2") (pinfunction "2_2") (pintype "passive"))
      (node (ref "PAD19") (pin "1") (pinfunction "P_1") (pintype "passive"))
    )
    (net (code "110") (name "Net-(PAD20-P)") (class "Default")
      (node (ref "E38") (pin "16") (pinfunction "16_16") (pintype "passive"))
      (node (ref "PAD20") (pin "1") (pinfunction "P_1") (pintype "passive"))
    )
    (net (code "111") (name "Net-(PAD21-P)") (class "Default")
      (node (ref "E38") (pin "15") (pinfunction "15_15") (pintype "passive"))
      (node (ref "PAD21") (pin "1") (pinfunction "P_1") (pintype "passive"))
    )
    (net (code "112") (name "Net-(PAD22-P)") (class "Default")
      (node (ref "E38") (pin "14") (pinfunction "14_14") (pintype "passive"))
      (node (ref "PAD22") (pin "1") (pinfunction "P_1") (pintype "passive"))
    )
    (net (code "113") (name "Net-(PAD23-P)") (class "Default")
      (node (ref "E38") (pin "13") (pinfunction "13_13") (pintype "passive"))
      (node (ref "PAD23") (pin "1") (pinfunction "P_1") (pintype "passive"))
    )
    (net (code "114") (name "Net-(PAD24-P)") (class "Default")
      (node (ref "E38") (pin "12") (pinfunction "12_12") (pintype "passive"))
      (node (ref "PAD24") (pin "1") (pinfunction "P_1") (pintype "passive"))
    )
    (net (code "115") (name "Net-(PAD25-P)") (class "Default")
      (node (ref "E38") (pin "11") (pinfunction "11_11") (pintype "passive"))
      (node (ref "PAD25") (pin "1") (pinfunction "P_1") (pintype "passive"))
    )
    (net (code "116") (name "Net-(PAD26-P)") (class "Default")
      (node (ref "E38") (pin "10") (pinfunction "10_10") (pintype "passive"))
      (node (ref "PAD26") (pin "1") (pinfunction "P_1") (pintype "passive"))
    )
    (net (code "117") (name "Net-(PAD27-P)") (class "Default")
      (node (ref "E38") (pin "9") (pinfunction "9_9") (pintype "passive"))
      (node (ref "PAD27") (pin "1") (pinfunction "P_1") (pintype "passive"))
    )
    (net (code "118") (name "Net-(PAD28-P)") (class "Default")
      (node (ref "E40") (pin "3") (pinfunction "3_3") (pintype "passive"))
      (node (ref "PAD28") (pin "1") (pinfunction "P_1") (pintype "passive"))
    )
    (net (code "119") (name "Net-(PAD29-P)") (class "Default")
      (node (ref "E40") (pin "4") (pinfunction "4_4") (pintype "passive"))
      (node (ref "PAD29") (pin "1") (pinfunction "P_1") (pintype "passive"))
    )
    (net (code "120") (name "Net-(PAD30-P)") (class "Default")
      (node (ref "E40") (pin "5") (pinfunction "5_5") (pintype "passive"))
      (node (ref "PAD30") (pin "1") (pinfunction "P_1") (pintype "passive"))
    )
    (net (code "121") (name "Net-(PAD31-P)") (class "Default")
      (node (ref "E40") (pin "6") (pinfunction "6_6") (pintype "passive"))
      (node (ref "PAD31") (pin "1") (pinfunction "P_1") (pintype "passive"))
    )
    (net (code "122") (name "Net-(PAD32-P)") (class "Default")
      (node (ref "E40") (pin "7") (pinfunction "7_7") (pintype "passive"))
      (node (ref "PAD32") (pin "1") (pinfunction "P_1") (pintype "passive"))
    )
    (net (code "123") (name "Net-(PAD33-P)") (class "Default")
      (node (ref "E40") (pin "8") (pinfunction "8_8") (pintype "passive"))
      (node (ref "PAD33") (pin "1") (pinfunction "P_1") (pintype "passive"))
    )
    (net (code "124") (name "Net-(PAD34-P)") (class "Default")
      (node (ref "E40") (pin "16") (pinfunction "16_16") (pintype "passive"))
      (node (ref "PAD34") (pin "1") (pinfunction "P_1") (pintype "passive"))
    )
    (net (code "125") (name "Net-(PAD35-P)") (class "Default")
      (node (ref "E40") (pin "15") (pinfunction "15_15") (pintype "passive"))
      (node (ref "PAD35") (pin "1") (pinfunction "P_1") (pintype "passive"))
    )
    (net (code "126") (name "Net-(PAD36-P)") (class "Default")
      (node (ref "E40") (pin "14") (pinfunction "14_14") (pintype "passive"))
      (node (ref "PAD36") (pin "1") (pinfunction "P_1") (pintype "passive"))
    )
    (net (code "127") (name "Net-(PAD37-P)") (class "Default")
      (node (ref "E40") (pin "13") (pinfunction "13_13") (pintype "passive"))
      (node (ref "PAD37") (pin "1") (pinfunction "P_1") (pintype "passive"))
    )
    (net (code "128") (name "Net-(PAD38-P)") (class "Default")
      (node (ref "E40") (pin "12") (pinfunction "12_12") (pintype "passive"))
      (node (ref "PAD38") (pin "1") (pinfunction "P_1") (pintype "passive"))
    )
    (net (code "129") (name "Net-(PAD39-P)") (class "Default")
      (node (ref "E40") (pin "11") (pinfunction "11_11") (pintype "passive"))
      (node (ref "PAD39") (pin "1") (pinfunction "P_1") (pintype "passive"))
    )
    (net (code "130") (name "Net-(PAD40-P)") (class "Default")
      (node (ref "E40") (pin "10") (pinfunction "10_10") (pintype "passive"))
      (node (ref "PAD40") (pin "1") (pinfunction "P_1") (pintype "passive"))
    )
    (net (code "131") (name "Net-(PAD41-P)") (class "Default")
      (node (ref "E40") (pin "9") (pinfunction "9_9") (pintype "passive"))
      (node (ref "PAD41") (pin "1") (pinfunction "P_1") (pintype "passive"))
    )
    (net (code "132") (name "Net-(PAD42-P)") (class "Default")
      (node (ref "E39") (pin "1") (pinfunction "1_1") (pintype "passive"))
      (node (ref "PAD42") (pin "1") (pinfunction "P_1") (pintype "passive"))
    )
    (net (code "133") (name "Net-(PAD43-P)") (class "Default")
      (node (ref "E39") (pin "2") (pinfunction "2_2") (pintype "passive"))
      (node (ref "PAD43") (pin "1") (pinfunction "P_1") (pintype "passive"))
    )
    (net (code "134") (name "Net-(PAD44-P)") (class "Default")
      (node (ref "E39") (pin "3") (pinfunction "3_3") (pintype "passive"))
      (node (ref "PAD44") (pin "1") (pinfunction "P_1") (pintype "passive"))
    )
    (net (code "135") (name "Net-(PAD45-P)") (class "Default")
      (node (ref "E39") (pin "4") (pinfunction "4_4") (pintype "passive"))
      (node (ref "PAD45") (pin "1") (pinfunction "P_1") (pintype "passive"))
    )
    (net (code "136") (name "Net-(PAD46-P)") (class "Default")
      (node (ref "E39") (pin "5") (pinfunction "5_5") (pintype "passive"))
      (node (ref "PAD46") (pin "1") (pinfunction "P_1") (pintype "passive"))
    )
    (net (code "137") (name "Net-(PAD47-P)") (class "Default")
      (node (ref "E39") (pin "6") (pinfunction "6_6") (pintype "passive"))
      (node (ref "PAD47") (pin "1") (pinfunction "P_1") (pintype "passive"))
    )
    (net (code "138") (name "Net-(PAD48-P)") (class "Default")
      (node (ref "E39") (pin "7") (pinfunction "7_7") (pintype "passive"))
      (node (ref "PAD48") (pin "1") (pinfunction "P_1") (pintype "passive"))
    )
    (net (code "139") (name "Net-(PAD49-P)") (class "Default")
      (node (ref "E39") (pin "8") (pinfunction "8_8") (pintype "passive"))
      (node (ref "PAD49") (pin "1") (pinfunction "P_1") (pintype "passive"))
    )
    (net (code "140") (name "Net-(PAD50-P)") (class "Default")
      (node (ref "E39") (pin "16") (pinfunction "16_16") (pintype "passive"))
      (node (ref "PAD50") (pin "1") (pinfunction "P_1") (pintype "passive"))
    )
    (net (code "141") (name "Net-(PAD51-P)") (class "Default")
      (node (ref "E39") (pin "15") (pinfunction "15_15") (pintype "passive"))
      (node (ref "PAD51") (pin "1") (pinfunction "P_1") (pintype "passive"))
    )
    (net (code "142") (name "Net-(PAD52-P)") (class "Default")
      (node (ref "E39") (pin "14") (pinfunction "14_14") (pintype "passive"))
      (node (ref "PAD52") (pin "1") (pinfunction "P_1") (pintype "passive"))
    )
    (net (code "143") (name "Net-(PAD53-P)") (class "Default")
      (node (ref "E39") (pin "13") (pinfunction "13_13") (pintype "passive"))
      (node (ref "PAD53") (pin "1") (pinfunction "P_1") (pintype "passive"))
    )
    (net (code "144") (name "Net-(PAD54-P)") (class "Default")
      (node (ref "E39") (pin "12") (pinfunction "12_12") (pintype "passive"))
      (node (ref "PAD54") (pin "1") (pinfunction "P_1") (pintype "passive"))
    )
    (net (code "145") (name "Net-(PAD55-P)") (class "Default")
      (node (ref "E39") (pin "11") (pinfunction "11_11") (pintype "passive"))
      (node (ref "PAD55") (pin "1") (pinfunction "P_1") (pintype "passive"))
    )
    (net (code "146") (name "Net-(PAD56-P)") (class "Default")
      (node (ref "E39") (pin "10") (pinfunction "10_10") (pintype "passive"))
      (node (ref "PAD56") (pin "1") (pinfunction "P_1") (pintype "passive"))
    )
    (net (code "147") (name "Net-(PAD57-P)") (class "Default")
      (node (ref "E39") (pin "9") (pinfunction "9_9") (pintype "passive"))
      (node (ref "PAD57") (pin "1") (pinfunction "P_1") (pintype "passive"))
    )
    (net (code "148") (name "PARITY") (class "Default")
      (node (ref "E15") (pin "1") (pinfunction "I0_1") (pintype "input"))
      (node (ref "E15") (pin "13") (pinfunction "I1_13") (pintype "input"))
      (node (ref "E15") (pin "2") (pinfunction "I1_2") (pintype "input"))
      (node (ref "E4") (pin "15") (pinfunction "RCO_15") (pintype "output"))
    )
    (net (code "149") (name "RD") (class "Default")
      (node (ref "E25") (pin "1") (pinfunction "I_1") (pintype "input"))
      (node (ref "E32") (pin "10") (pinfunction "I1_10") (pintype "input"))
      (node (ref "E35") (pin "10") (pinfunction "O_10") (pintype "output"))
    )
    (net (code "150") (name "RUN") (class "Default")
      (node (ref "E30") (pin "9") (pinfunction "Q_9") (pintype "output"))
      (node (ref "E36") (pin "11") (pinfunction "I0_11") (pintype "input"))
      (node (ref "IC9") (pin "6") (pinfunction "I0_6") (pintype "input"))
      (node (ref "IC9") (pin "7") (pinfunction "I1_7") (pintype "input"))
    )
    (net (code "151") (name "RX_DATA") (class "Default")
      (node (ref "E22") (pin "2") (pinfunction "J_2") (pintype "input"))
      (node (ref "E22") (pin "3") (pinfunction "K_3") (pintype "input"))
      (node (ref "E35") (pin "1") (pinfunction "O_1") (pintype "output"))
    )
    (net (code "152") (name "SHIFT") (class "Default")
      (node (ref "E32") (pin "3") (pinfunction "I0_3") (pintype "input"))
      (node (ref "E35") (pin "4") (pinfunction "O_4") (pintype "output"))
    )
    (net (code "153") (name "VCC") (class "Default")
      (node (ref "C1") (pin "1") (pinfunction "1_1") (pintype "passive"))
      (node (ref "C10") (pin "1") (pinfunction "1_1") (pintype "passive"))
      (node (ref "C11") (pin "1") (pinfunction "1_1") (pintype "passive"))
      (node (ref "C12") (pin "1") (pinfunction "1_1") (pintype "passive"))
      (node (ref "C13") (pin "1") (pinfunction "1_1") (pintype "passive"))
      (node (ref "C14") (pin "1") (pinfunction "1_1") (pintype "passive"))
      (node (ref "C15") (pin "1") (pinfunction "1_1") (pintype "passive"))
      (node (ref "C16") (pin "1") (pinfunction "1_1") (pintype "passive"))
      (node (ref "C17") (pin "1") (pinfunction "1_1") (pintype "passive"))
      (node (ref "C18") (pin "1") (pinfunction "1_1") (pintype "passive"))
      (node (ref "C19") (pin "1") (pinfunction "1_1") (pintype "passive"))
      (node (ref "C2") (pin "1") (pinfunction "1_1") (pintype "passive"))
      (node (ref "C20") (pin "1") (pinfunction "1_1") (pintype "passive"))
      (node (ref "C21") (pin "1") (pinfunction "1_1") (pintype "passive"))
      (node (ref "C22") (pin "1") (pinfunction "1_1") (pintype "passive"))
      (node (ref "C23") (pin "1") (pinfunction "1_1") (pintype "passive"))
      (node (ref "C24") (pin "1") (pinfunction "1_1") (pintype "passive"))
      (node (ref "C25") (pin "1") (pinfunction "1_1") (pintype "passive"))
      (node (ref "C26") (pin "1") (pinfunction "1_1") (pintype "passive"))
      (node (ref "C27") (pin "1") (pinfunction "1_1") (pintype "passive"))
      (node (ref "C28") (pin "1") (pinfunction "1_1") (pintype "passive"))
      (node (ref "C29") (pin "1") (pinfunction "1_1") (pintype "passive"))
      (node (ref "C3") (pin "1") (pinfunction "1_1") (pintype "passive"))
      (node (ref "C30") (pin "1") (pinfunction "1_1") (pintype "passive"))
      (node (ref "C31") (pin "1") (pinfunction "1_1") (pintype "passive"))
      (node (ref "C32") (pin "1") (pinfunction "1_1") (pintype "passive"))
      (node (ref "C33") (pin "1") (pinfunction "1_1") (pintype "passive"))
      (node (ref "C34") (pin "1") (pinfunction "1_1") (pintype "passive"))
      (node (ref "C35") (pin "1") (pinfunction "1_1") (pintype "passive"))
      (node (ref "C36") (pin "1") (pinfunction "1_1") (pintype "passive"))
      (node (ref "C37") (pin "1") (pinfunction "1_1") (pintype "passive"))
      (node (ref "C38") (pin "1") (pinfunction "1_1") (pintype "passive"))
      (node (ref "C39") (pin "1") (pinfunction "1_1") (pintype "passive"))
      (node (ref "C4") (pin "1") (pinfunction "1_1") (pintype "passive"))
      (node (ref "C40") (pin "+") (pinfunction "+_+") (pintype "passive"))
      (node (ref "C5") (pin "1") (pinfunction "1_1") (pintype "passive"))
      (node (ref "C6") (pin "1") (pinfunction "1_1") (pintype "passive"))
      (node (ref "C7") (pin "1") (pinfunction "1_1") (pintype "passive"))
      (node (ref "C8") (pin "1") (pinfunction "1_1") (pintype "passive"))
      (node (ref "C9") (pin "1") (pinfunction "1_1") (pintype "passive"))
      (node (ref "E1") (pin "4") (pinfunction "I1_4") (pintype "input"))
      (node (ref "E1") (pin "5") (pinfunction "I2_5") (pintype "input"))
      (node (ref "E14") (pin "6") (pinfunction "G1_6") (pintype "input"))
      (node (ref "E16") (pin "10") (pinfunction "PRE_10") (pintype "input"))
      (node (ref "E16") (pin "4") (pinfunction "PRE_4") (pintype "input"))
      (node (ref "E17") (pin "7") (pinfunction "PRE_7") (pintype "input"))
      (node (ref "E18") (pin "10") (pinfunction "PRE_10") (pintype "input"))
      (node (ref "E18") (pin "2") (pinfunction "D_2") (pintype "input"))
      (node (ref "E19") (pin "10") (pinfunction "PRE_10") (pintype "input"))
      (node (ref "E19") (pin "2") (pinfunction "D_2") (pintype "input"))
      (node (ref "E2") (pin "10") (pinfunction "PRE_10") (pintype "input"))
      (node (ref "E2") (pin "13") (pinfunction "CLR_13") (pintype "input"))
      (node (ref "E25") (pin "11") (pinfunction "I_11") (pintype "input"))
      (node (ref "E25") (pin "13") (pinfunction "I_13") (pintype "input"))
      (node (ref "E26") (pin "10") (pinfunction "PRE_10") (pintype "input"))
      (node (ref "E26") (pin "2") (pinfunction "D_2") (pintype "input"))
      (node (ref "E30") (pin "10") (pinfunction "PRE_10") (pintype "input"))
      (node (ref "E30") (pin "12") (pinfunction "D_12") (pintype "input"))
      (node (ref "E30") (pin "4") (pinfunction "PRE_4") (pintype "input"))
      (node (ref "R1") (pin "2") (pinfunction "2_2") (pintype "passive"))
      (node (ref "R18") (pin "2") (pinfunction "2_2") (pintype "passive"))
      (node (ref "R19") (pin "1") (pinfunction "1_1") (pintype "passive"))
      (node (ref "R2") (pin "2") (pinfunction "2_2") (pintype "passive"))
      (node (ref "R20") (pin "2") (pinfunction "2_2") (pintype "passive"))
      (node (ref "R3") (pin "2") (pinfunction "2_2") (pintype "passive"))
      (node (ref "R4") (pin "2") (pinfunction "2_2") (pintype "passive"))
      (node (ref "R5") (pin "2") (pinfunction "2_2") (pintype "passive"))
      (node (ref "R6") (pin "2") (pinfunction "2_2") (pintype "passive"))
      (node (ref "R7") (pin "2") (pinfunction "2_2") (pintype "passive"))
      (node (ref "R8") (pin "2") (pinfunction "2_2") (pintype "passive"))
      (node (ref "R9") (pin "2") (pinfunction "2_2") (pintype "passive"))
      (node (ref "SL1") (pin "1") (pinfunction "S_1") (pintype "passive"))
    )
    (net (code "154") (name "WRT") (class "Default")
      (node (ref "E10") (pin "5") (pinfunction "I2_5") (pintype "input"))
      (node (ref "E15") (pin "10") (pinfunction "I1_10") (pintype "input"))
      (node (ref "E25") (pin "2") (pinfunction "O_2") (pintype "output"))
      (node (ref "IC7") (pin "6") (pinfunction "I0_6") (pintype "input"))
    )
    (net (code "155") (name "XDR2") (class "Default")
      (node (ref "E10") (pin "2") (pinfunction "I1_2") (pintype "input"))
      (node (ref "E5") (pin "12") (pinfunction "I0_12") (pintype "input"))
      (node (ref "E5") (pin "8") (pinfunction "O_8") (pintype "output"))
    )
    (net (code "156") (name "XFER_REQ") (class "Default")
      (node (ref "E19") (pin "3") (pinfunction "CLK_3") (pintype "input"))
      (node (ref "E20") (pin "12") (pinfunction "I0_12") (pintype "input"))
      (node (ref "E36") (pin "4") (pinfunction "O_4") (pintype "output"))
    )
    (net (code "157") (name "unconnected-(D34L1-2-PadB)") (class "Default")
      (node (ref "D34L1") (pin "B") (pinfunction "2_B") (pintype "bidirectional"))
    )
    (net (code "158") (name "unconnected-(D34L1-34-PadNN)") (class "Default")
      (node (ref "D34L1") (pin "NN") (pinfunction "34_NN") (pintype "bidirectional"))
    )
    (net (code "159") (name "unconnected-(D34L1-38-PadTT)") (class "Default")
      (node (ref "D34L1") (pin "TT") (pinfunction "38_TT") (pintype "bidirectional"))
    )
    (net (code "160") (name "unconnected-(D34L1-40-PadVV)") (class "Default")
      (node (ref "D34L1") (pin "VV") (pinfunction "40_VV") (pintype "bidirectional"))
    )
    (net (code "161") (name "unconnected-(D34L2-2-PadB)") (class "Default")
      (node (ref "D34L2") (pin "B") (pinfunction "2_B") (pintype "bidirectional"))
    )
    (net (code "162") (name "unconnected-(D34L2-34-PadNN)") (class "Default")
      (node (ref "D34L2") (pin "NN") (pinfunction "34_NN") (pintype "bidirectional"))
    )
    (net (code "163") (name "unconnected-(D34L2-38-PadTT)") (class "Default")
      (node (ref "D34L2") (pin "TT") (pinfunction "38_TT") (pintype "bidirectional"))
    )
    (net (code "164") (name "unconnected-(D34L2-40-PadVV)") (class "Default")
      (node (ref "D34L2") (pin "VV") (pinfunction "40_VV") (pintype "bidirectional"))
    )
    (net (code "165") (name "unconnected-(D35L1-2-PadB)") (class "Default")
      (node (ref "D35L1") (pin "B") (pinfunction "2_B") (pintype "bidirectional"))
    )
    (net (code "166") (name "unconnected-(D35L1-40-PadVV)") (class "Default")
      (node (ref "D35L1") (pin "VV") (pinfunction "40_VV") (pintype "bidirectional"))
    )
    (net (code "167") (name "unconnected-(D35L2-2-PadB)") (class "Default")
      (node (ref "D35L2") (pin "B") (pinfunction "2_B") (pintype "bidirectional"))
    )
    (net (code "168") (name "unconnected-(D35L2-40-PadVV)") (class "Default")
      (node (ref "D35L2") (pin "VV") (pinfunction "40_VV") (pintype "bidirectional"))
    )
    (net (code "169") (name "unconnected-(D36L1-2-PadB)") (class "Default")
      (node (ref "D36L1") (pin "B") (pinfunction "2_B") (pintype "bidirectional"))
    )
    (net (code "170") (name "unconnected-(D36L1-40-PadVV)") (class "Default")
      (node (ref "D36L1") (pin "VV") (pinfunction "40_VV") (pintype "bidirectional"))
    )
    (net (code "171") (name "unconnected-(D36L2-2-PadB)") (class "Default")
      (node (ref "D36L2") (pin "B") (pinfunction "2_B") (pintype "bidirectional"))
    )
    (net (code "172") (name "unconnected-(D36L2-40-PadVV)") (class "Default")
      (node (ref "D36L2") (pin "VV") (pinfunction "40_VV") (pintype "bidirectional"))
    )
    (net (code "173") (name "unconnected-(E2A-Q-Pad5)") (class "Default")
      (node (ref "E2") (pin "5") (pinfunction "Q_5") (pintype "output"))
    )
    (net (code "174") (name "unconnected-(E2B-Q-Pad9)") (class "Default")
      (node (ref "E2") (pin "9") (pinfunction "Q_9") (pintype "output"))
    )
    (net (code "175") (name "unconnected-(E2B-~{Q}-Pad8)") (class "Default")
      (node (ref "E2") (pin "8") (pinfunction "~{Q}_8") (pintype "output"))
    )
    (net (code "176") (name "unconnected-(E4A-QA-Pad14)") (class "Default")
      (node (ref "E4") (pin "14") (pinfunction "QA_14") (pintype "output"))
    )
    (net (code "177") (name "unconnected-(E4A-QB-Pad13)") (class "Default")
      (node (ref "E4") (pin "13") (pinfunction "QB_13") (pintype "output"))
    )
    (net (code "178") (name "unconnected-(E4A-QC-Pad12)") (class "Default")
      (node (ref "E4") (pin "12") (pinfunction "QC_12") (pintype "output"))
    )
    (net (code "179") (name "unconnected-(E4A-QD-Pad11)") (class "Default")
      (node (ref "E4") (pin "11") (pinfunction "QD_11") (pintype "output"))
    )
    (net (code "180") (name "unconnected-(E11A-Y0-Pad15)") (class "Default")
      (node (ref "E11") (pin "15") (pinfunction "Y0_15") (pintype "output"))
    )
    (net (code "181") (name "unconnected-(E11A-Y2-Pad13)") (class "Default")
      (node (ref "E11") (pin "13") (pinfunction "Y2_13") (pintype "output"))
    )
    (net (code "182") (name "unconnected-(E11A-Y3-Pad12)") (class "Default")
      (node (ref "E11") (pin "12") (pinfunction "Y3_12") (pintype "output"))
    )
    (net (code "183") (name "unconnected-(E11A-Y4-Pad11)") (class "Default")
      (node (ref "E11") (pin "11") (pinfunction "Y4_11") (pintype "output"))
    )
    (net (code "184") (name "unconnected-(E11A-Y5-Pad10)") (class "Default")
      (node (ref "E11") (pin "10") (pinfunction "Y5_10") (pintype "output"))
    )
    (net (code "185") (name "unconnected-(E11A-Y6-Pad9)") (class "Default")
      (node (ref "E11") (pin "9") (pinfunction "Y6_9") (pintype "output"))
    )
    (net (code "186") (name "unconnected-(E12A-Y0-Pad15)") (class "Default")
      (node (ref "E12") (pin "15") (pinfunction "Y0_15") (pintype "output"))
    )
    (net (code "187") (name "unconnected-(E12A-Y1-Pad14)") (class "Default")
      (node (ref "E12") (pin "14") (pinfunction "Y1_14") (pintype "output"))
    )
    (net (code "188") (name "unconnected-(E12A-Y4-Pad11)") (class "Default")
      (node (ref "E12") (pin "11") (pinfunction "Y4_11") (pintype "output"))
    )
    (net (code "189") (name "unconnected-(E12A-Y5-Pad10)") (class "Default")
      (node (ref "E12") (pin "10") (pinfunction "Y5_10") (pintype "output"))
    )
    (net (code "190") (name "unconnected-(E12A-Y6-Pad9)") (class "Default")
      (node (ref "E12") (pin "9") (pinfunction "Y6_9") (pintype "output"))
    )
    (net (code "191") (name "unconnected-(E12A-Y7-Pad7)") (class "Default")
      (node (ref "E12") (pin "7") (pinfunction "Y7_7") (pintype "output"))
    )
    (net (code "192") (name "unconnected-(E13A-Y0-Pad15)") (class "Default")
      (node (ref "E13") (pin "15") (pinfunction "Y0_15") (pintype "output"))
    )
    (net (code "193") (name "unconnected-(E13A-Y1-Pad14)") (class "Default")
      (node (ref "E13") (pin "14") (pinfunction "Y1_14") (pintype "output"))
    )
    (net (code "194") (name "unconnected-(E13A-Y2-Pad13)") (class "Default")
      (node (ref "E13") (pin "13") (pinfunction "Y2_13") (pintype "output"))
    )
    (net (code "195") (name "unconnected-(E13A-Y3-Pad12)") (class "Default")
      (node (ref "E13") (pin "12") (pinfunction "Y3_12") (pintype "output"))
    )
    (net (code "196") (name "unconnected-(E17B-Q-Pad11)") (class "Default")
      (node (ref "E17") (pin "11") (pinfunction "Q_11") (pintype "output"))
    )
    (net (code "197") (name "unconnected-(E18A-~{Q}-Pad6)") (class "Default")
      (node (ref "E18") (pin "6") (pinfunction "~{Q}_6") (pintype "output"))
    )
    (net (code "198") (name "unconnected-(E19A-~{Q}-Pad6)") (class "Default")
      (node (ref "E19") (pin "6") (pinfunction "~{Q}_6") (pintype "output"))
    )
    (net (code "199") (name "unconnected-(E19B-Q-Pad9)") (class "Default")
      (node (ref "E19") (pin "9") (pinfunction "Q_9") (pintype "output"))
    )
    (net (code "200") (name "unconnected-(E21A-~{QD}-Pad11)") (class "Default")
      (node (ref "E21") (pin "11") (pinfunction "~{QD}_11") (pintype "output"))
    )
    (net (code "201") (name "unconnected-(E22A-~{QD}-Pad11)") (class "Default")
      (node (ref "E22") (pin "11") (pinfunction "~{QD}_11") (pintype "output"))
    )
    (net (code "202") (name "unconnected-(E23A-~{QD}-Pad11)") (class "Default")
      (node (ref "E23") (pin "11") (pinfunction "~{QD}_11") (pintype "output"))
    )
    (net (code "203") (name "unconnected-(E26A-~{Q}-Pad6)") (class "Default")
      (node (ref "E26") (pin "6") (pinfunction "~{Q}_6") (pintype "output"))
    )
    (net (code "204") (name "unconnected-(E26B-Q-Pad9)") (class "Default")
      (node (ref "E26") (pin "9") (pinfunction "Q_9") (pintype "output"))
    )
    (net (code "205") (name "unconnected-(E30A-~{Q}-Pad6)") (class "Default")
      (node (ref "E30") (pin "6") (pinfunction "~{Q}_6") (pintype "output"))
    )
    (net (code "206") (name "unconnected-(E30B-~{Q}-Pad8)") (class "Default")
      (node (ref "E30") (pin "8") (pinfunction "~{Q}_8") (pintype "output"))
    )
    (net (code "207") (name "unconnected-(LASTDEV-Pad8)") (class "Default")
      (node (ref "LASTDEV") (pin "8") (pinfunction "8_8") (pintype "passive"))
    )
    (net (code "208") (name "unconnected-(LASTDEV-Pad9)") (class "Default")
      (node (ref "LASTDEV") (pin "9") (pinfunction "9_9") (pintype "passive"))
    )
    (net (code "209") (name "unconnected-(LASTDEV-Pad10)") (class "Default")
      (node (ref "LASTDEV") (pin "10") (pinfunction "10_10") (pintype "passive"))
    )
    (net (code "210") (name "~{ACB00}") (class "Default")
      (node (ref "D34L1") (pin "D") (pinfunction "4_D") (pintype "bidirectional"))
      (node (ref "D34L2") (pin "D") (pinfunction "4_D") (pintype "bidirectional"))
      (node (ref "IC6") (pin "3") (pinfunction "O_3") (pintype "open_collector"))
    )
    (net (code "211") (name "~{ACB01}") (class "Default")
      (node (ref "D34L1") (pin "J") (pinfunction "8_J") (pintype "bidirectional"))
      (node (ref "D34L2") (pin "J") (pinfunction "8_J") (pintype "bidirectional"))
      (node (ref "IC6") (pin "5") (pinfunction "O_5") (pintype "open_collector"))
    )
    (net (code "212") (name "~{ACB02}") (class "Default")
      (node (ref "D34L1") (pin "N") (pinfunction "12_N") (pintype "bidirectional"))
      (node (ref "D34L2") (pin "N") (pinfunction "12_N") (pintype "bidirectional"))
      (node (ref "IC1") (pin "3") (pinfunction "O_3") (pintype "open_collector"))
    )
    (net (code "213") (name "~{ACB03}") (class "Default")
      (node (ref "D34L1") (pin "T") (pinfunction "16_T") (pintype "bidirectional"))
      (node (ref "D34L2") (pin "T") (pinfunction "16_T") (pintype "bidirectional"))
      (node (ref "IC2") (pin "5") (pinfunction "O_5") (pintype "open_collector"))
    )
    (net (code "214") (name "~{ACB04}") (class "Default")
      (node (ref "D34L1") (pin "X") (pinfunction "20_X") (pintype "bidirectional"))
      (node (ref "D34L2") (pin "X") (pinfunction "20_X") (pintype "bidirectional"))
      (node (ref "IC1") (pin "5") (pinfunction "O_5") (pintype "open_collector"))
    )
    (net (code "215") (name "~{ACB05}") (class "Default")
      (node (ref "D34L1") (pin "BB") (pinfunction "24_BB") (pintype "bidirectional"))
      (node (ref "D34L2") (pin "BB") (pinfunction "24_BB") (pintype "bidirectional"))
      (node (ref "IC4") (pin "3") (pinfunction "O_3") (pintype "open_collector"))
    )
    (net (code "216") (name "~{ACB06}") (class "Default")
      (node (ref "D34L1") (pin "FF") (pinfunction "28_FF") (pintype "bidirectional"))
      (node (ref "D34L2") (pin "FF") (pinfunction "28_FF") (pintype "bidirectional"))
      (node (ref "IC3") (pin "3") (pinfunction "O_3") (pintype "open_collector"))
    )
    (net (code "217") (name "~{ACB07}") (class "Default")
      (node (ref "D34L1") (pin "LL") (pinfunction "32_LL") (pintype "bidirectional"))
      (node (ref "D34L2") (pin "LL") (pinfunction "32_LL") (pintype "bidirectional"))
      (node (ref "IC3") (pin "5") (pinfunction "O_5") (pintype "open_collector"))
    )
    (net (code "218") (name "~{ACB08}") (class "Default")
      (node (ref "D34L1") (pin "RR") (pinfunction "36_RR") (pintype "bidirectional"))
      (node (ref "D34L2") (pin "RR") (pinfunction "36_RR") (pintype "bidirectional"))
      (node (ref "IC4") (pin "5") (pinfunction "O_5") (pintype "open_collector"))
    )
    (net (code "219") (name "~{ACB09}") (class "Default")
      (node (ref "D34L1") (pin "F") (pinfunction "6_F") (pintype "bidirectional"))
      (node (ref "D34L2") (pin "F") (pinfunction "6_F") (pintype "bidirectional"))
      (node (ref "IC5") (pin "3") (pinfunction "O_3") (pintype "open_collector"))
    )
    (net (code "220") (name "~{ACB10}") (class "Default")
      (node (ref "D34L1") (pin "L") (pinfunction "10_L") (pintype "bidirectional"))
      (node (ref "D34L2") (pin "L") (pinfunction "10_L") (pintype "bidirectional"))
      (node (ref "IC5") (pin "5") (pinfunction "O_5") (pintype "open_collector"))
    )
    (net (code "221") (name "~{ACB11}") (class "Default")
      (node (ref "D34L1") (pin "R") (pinfunction "14_R") (pintype "bidirectional"))
      (node (ref "D34L2") (pin "R") (pinfunction "14_R") (pintype "bidirectional"))
      (node (ref "IC2") (pin "3") (pinfunction "O_3") (pintype "open_collector"))
    )
    (net (code "222") (name "~{ACCLEAR}") (class "Default")
      (node (ref "D34L1") (pin "DD") (pinfunction "26_DD") (pintype "bidirectional"))
      (node (ref "D34L2") (pin "DD") (pinfunction "26_DD") (pintype "bidirectional"))
      (node (ref "IC7") (pin "3") (pinfunction "O_3") (pintype "open_collector"))
    )
    (net (code "223") (name "~{BMB03}") (class "Default")
      (node (ref "D35L1") (pin "T") (pinfunction "16_T") (pintype "bidirectional"))
      (node (ref "D35L2") (pin "T") (pinfunction "16_T") (pintype "bidirectional"))
    )
    (net (code "224") (name "~{BMB04}") (class "Default")
      (node (ref "D35L1") (pin "BB") (pinfunction "24_BB") (pintype "bidirectional"))
      (node (ref "D35L2") (pin "BB") (pinfunction "24_BB") (pintype "bidirectional"))
    )
    (net (code "225") (name "~{BMB05}") (class "Default")
      (node (ref "D35L1") (pin "LL") (pinfunction "32_LL") (pintype "bidirectional"))
      (node (ref "D35L2") (pin "LL") (pinfunction "32_LL") (pintype "bidirectional"))
    )
    (net (code "226") (name "~{BMB06}") (class "Default")
      (node (ref "D35L1") (pin "F") (pinfunction "6_F") (pintype "bidirectional"))
      (node (ref "D35L2") (pin "F") (pinfunction "6_F") (pintype "bidirectional"))
    )
    (net (code "227") (name "~{BMB07}") (class "Default")
      (node (ref "D35L1") (pin "R") (pinfunction "14_R") (pintype "bidirectional"))
      (node (ref "D35L2") (pin "R") (pinfunction "14_R") (pintype "bidirectional"))
    )
    (net (code "228") (name "~{BMB08}") (class "Default")
      (node (ref "D35L1") (pin "Z") (pinfunction "22_Z") (pintype "bidirectional"))
      (node (ref "D35L2") (pin "Z") (pinfunction "22_Z") (pintype "bidirectional"))
    )
    (net (code "229") (name "~{BRUN}") (class "Default")
      (node (ref "D34L1") (pin "JJ") (pinfunction "30_JJ") (pintype "bidirectional"))
      (node (ref "D34L2") (pin "JJ") (pinfunction "30_JJ") (pintype "bidirectional"))
    )
    (net (code "230") (name "~{CLK_PARITY}") (class "Default")
      (node (ref "E17") (pin "6") (pinfunction "CLK_6") (pintype "input"))
      (node (ref "E32") (pin "6") (pinfunction "O_6") (pintype "output"))
      (node (ref "E5") (pin "4") (pinfunction "I0_4") (pintype "input"))
      (node (ref "E5") (pin "5") (pinfunction "I1_5") (pintype "input"))
    )
    (net (code "231") (name "~{DONE_SKIP}") (class "Default")
      (node (ref "E18") (pin "1") (pinfunction "CLR_1") (pintype "input"))
      (node (ref "E20") (pin "8") (pinfunction "O_8") (pintype "output"))
      (node (ref "E6") (pin "5") (pinfunction "I1_5") (pintype "input"))
    )
    (net (code "232") (name "~{DONE}") (class "Default")
      (node (ref "E10") (pin "4") (pinfunction "I1_4") (pintype "input"))
      (node (ref "E25") (pin "4") (pinfunction "O_4") (pintype "output"))
      (node (ref "E31") (pin "12") (pinfunction "I2_12") (pintype "input"))
    )
    (net (code "233") (name "~{ENB_BUF_LD}") (class "Default")
      (node (ref "E21") (pin "9") (pinfunction "S/~{L}_9") (pintype "input"))
      (node (ref "E22") (pin "9") (pinfunction "S/~{L}_9") (pintype "input"))
      (node (ref "E23") (pin "9") (pinfunction "S/~{L}_9") (pintype "input"))
      (node (ref "E24") (pin "11") (pinfunction "O_11") (pintype "output"))
      (node (ref "E32") (pin "13") (pinfunction "I2_13") (pintype "input"))
      (node (ref "E32") (pin "2") (pinfunction "I1_2") (pintype "input"))
      (node (ref "E4") (pin "9") (pinfunction "LD_9") (pintype "input"))
    )
    (net (code "234") (name "~{ERR_SKIP}") (class "Default")
      (node (ref "E20") (pin "6") (pinfunction "O_6") (pintype "output"))
      (node (ref "E26") (pin "1") (pinfunction "CLR_1") (pintype "input"))
      (node (ref "E6") (pin "4") (pinfunction "I0_4") (pintype "input"))
    )
    (net (code "235") (name "~{INIT1}") (class "Default")
      (node (ref "E11") (pin "7") (pinfunction "Y7_7") (pintype "output"))
      (node (ref "E2") (pin "4") (pinfunction "PRE_4") (pintype "input"))
    )
    (net (code "236") (name "~{INIT4}") (class "Default")
      (node (ref "E13") (pin "7") (pinfunction "Y7_7") (pintype "output"))
      (node (ref "E2") (pin "3") (pinfunction "CLK_3") (pintype "input"))
    )
    (net (code "237") (name "~{INIT}") (class "Default")
      (node (ref "E15") (pin "6") (pinfunction "O_6") (pintype "output"))
      (node (ref "E16") (pin "1") (pinfunction "CLR_1") (pintype "input"))
      (node (ref "E16") (pin "13") (pinfunction "CLR_13") (pintype "input"))
      (node (ref "E18") (pin "13") (pinfunction "CLR_13") (pintype "input"))
      (node (ref "E19") (pin "13") (pinfunction "CLR_13") (pintype "input"))
      (node (ref "E21") (pin "1") (pinfunction "CLR_1") (pintype "input"))
      (node (ref "E22") (pin "1") (pinfunction "CLR_1") (pintype "input"))
      (node (ref "E23") (pin "1") (pinfunction "CLR_1") (pintype "input"))
      (node (ref "E24") (pin "9") (pinfunction "I0_9") (pintype "input"))
      (node (ref "E26") (pin "13") (pinfunction "CLR_13") (pintype "input"))
      (node (ref "E30") (pin "1") (pinfunction "CLR_1") (pintype "input"))
      (node (ref "E4") (pin "1") (pinfunction "CLR_1") (pintype "input"))
    )
    (net (code "238") (name "~{INTR4}") (class "Default")
      (node (ref "E13") (pin "9") (pinfunction "Y6_9") (pintype "output"))
      (node (ref "E30") (pin "3") (pinfunction "CLK_3") (pintype "input"))
    )
    (net (code "239") (name "~{INT_RQ}") (class "Default")
      (node (ref "D34L1") (pin "Z") (pinfunction "22_Z") (pintype "bidirectional"))
      (node (ref "D34L2") (pin "Z") (pinfunction "22_Z") (pintype "bidirectional"))
      (node (ref "IC10") (pin "5") (pinfunction "O_5") (pintype "open_collector"))
    )
    (net (code "240") (name "~{IOS}") (class "Default")
      (node (ref "D34L1") (pin "V") (pinfunction "18_V") (pintype "bidirectional"))
      (node (ref "D34L2") (pin "V") (pinfunction "18_V") (pintype "bidirectional"))
      (node (ref "IC10") (pin "3") (pinfunction "O_3") (pintype "open_collector"))
    )
    (net (code "241") (name "~{LCD1}") (class "Default")
      (node (ref "E10") (pin "9") (pinfunction "I0_9") (pintype "input"))
      (node (ref "E11") (pin "14") (pinfunction "Y1_14") (pintype "output"))
      (node (ref "E16") (pin "11") (pinfunction "CLK_11") (pintype "input"))
      (node (ref "E16") (pin "3") (pinfunction "CLK_3") (pintype "input"))
      (node (ref "E24") (pin "5") (pinfunction "I1_5") (pintype "input"))
      (node (ref "E25") (pin "5") (pinfunction "I_5") (pintype "input"))
    )
    (net (code "242") (name "~{MAINT}") (class "Default")
      (node (ref "E10") (pin "3") (pinfunction "I0_3") (pintype "input"))
      (node (ref "E16") (pin "8") (pinfunction "~{Q}_8") (pintype "output"))
      (node (ref "E18") (pin "4") (pinfunction "PRE_4") (pintype "input"))
      (node (ref "E19") (pin "4") (pinfunction "PRE_4") (pintype "input"))
      (node (ref "E24") (pin "13") (pinfunction "I1_13") (pintype "input"))
      (node (ref "E26") (pin "4") (pinfunction "PRE_4") (pintype "input"))
      (node (ref "E31") (pin "10") (pinfunction "I1_10") (pintype "input"))
      (node (ref "E31") (pin "5") (pinfunction "I3_5") (pintype "input"))
      (node (ref "E31") (pin "9") (pinfunction "I0_9") (pintype "input"))
    )
    (net (code "243") (name "~{MYDEV}") (class "Default")
      (node (ref "E11") (pin "4") (pinfunction "G2A_4") (pintype "input"))
      (node (ref "E12") (pin "4") (pinfunction "G2A_4") (pintype "input"))
      (node (ref "E13") (pin "4") (pinfunction "G2A_4") (pintype "input"))
      (node (ref "IOT") (pin "1") (pinfunction "P_1") (pintype "passive"))
    )
    (net (code "244") (name "~{PARITY}") (class "Default")
      (node (ref "E15") (pin "12") (pinfunction "I0_12") (pintype "input"))
      (node (ref "E17") (pin "10") (pinfunction "~{Q}_10") (pintype "output"))
    )
    (net (code "245") (name "~{RX_12_BIT}") (class "Default")
      (node (ref "DRIVE") (pin "FF") (pinfunction "28_FF") (pintype "bidirectional"))
      (node (ref "IC8") (pin "3") (pinfunction "O_3") (pintype "open_collector"))
      (node (ref "R16") (pin "2") (pinfunction "2_2") (pintype "passive"))
      (node (ref "R7") (pin "1") (pinfunction "1_1") (pintype "passive"))
    )
    (net (code "246") (name "~{RX_DATA}") (class "Default")
      (node (ref "DRIVE") (pin "BB") (pinfunction "24_BB") (pintype "bidirectional"))
      (node (ref "E35") (pin "2") (pinfunction "I0_2") (pintype "input"))
      (node (ref "IC7") (pin "5") (pinfunction "O_5") (pintype "open_collector"))
      (node (ref "R17") (pin "2") (pinfunction "2_2") (pintype "passive"))
      (node (ref "R8") (pin "1") (pinfunction "1_1") (pintype "passive"))
    )
    (net (code "247") (name "~{RX_DONE}") (class "Default")
      (node (ref "DRIVE") (pin "X") (pinfunction "20_X") (pintype "bidirectional"))
      (node (ref "E36") (pin "8") (pinfunction "I0_8") (pintype "input"))
      (node (ref "R13") (pin "2") (pinfunction "2_2") (pintype "passive"))
      (node (ref "R4") (pin "1") (pinfunction "1_1") (pintype "passive"))
    )
    (net (code "248") (name "~{RX_ERROR}") (class "Default")
      (node (ref "DRIVE") (pin "J") (pinfunction "8_J") (pintype "bidirectional"))
      (node (ref "E36") (pin "3") (pinfunction "I1_3") (pintype "input"))
      (node (ref "R14") (pin "2") (pinfunction "2_2") (pintype "passive"))
      (node (ref "R5") (pin "1") (pinfunction "1_1") (pintype "passive"))
    )
    (net (code "249") (name "~{RX_INIT}") (class "Default")
      (node (ref "DRIVE") (pin "N") (pinfunction "12_N") (pintype "bidirectional"))
      (node (ref "IC8") (pin "5") (pinfunction "O_5") (pintype "open_collector"))
      (node (ref "R20") (pin "1") (pinfunction "1_1") (pintype "passive"))
      (node (ref "R9") (pin "1") (pinfunction "1_1") (pintype "passive"))
    )
    (net (code "250") (name "~{RX_OUT}") (class "Default")
      (node (ref "DRIVE") (pin "RR") (pinfunction "36_RR") (pintype "bidirectional"))
      (node (ref "E35") (pin "8") (pinfunction "I0_8") (pintype "input"))
      (node (ref "R12") (pin "2") (pinfunction "2_2") (pintype "passive"))
      (node (ref "R3") (pin "1") (pinfunction "1_1") (pintype "passive"))
    )
    (net (code "251") (name "~{RX_RUN}") (class "Default")
      (node (ref "DRIVE") (pin "D") (pinfunction "4_D") (pintype "bidirectional"))
      (node (ref "IC9") (pin "5") (pinfunction "O_5") (pintype "open_collector"))
      (node (ref "R15") (pin "2") (pinfunction "2_2") (pintype "passive"))
      (node (ref "R6") (pin "1") (pinfunction "1_1") (pintype "passive"))
    )
    (net (code "252") (name "~{RX_SHIFT}") (class "Default")
      (node (ref "DRIVE") (pin "LL") (pinfunction "32_LL") (pintype "bidirectional"))
      (node (ref "E35") (pin "5") (pinfunction "I0_5") (pintype "input"))
      (node (ref "R10") (pin "2") (pinfunction "2_2") (pintype "passive"))
      (node (ref "R2") (pin "1") (pinfunction "1_1") (pintype "passive"))
    )
    (net (code "253") (name "~{RX_TR_REQ}") (class "Default")
      (node (ref "DRIVE") (pin "T") (pinfunction "16_T") (pintype "bidirectional"))
      (node (ref "E36") (pin "5") (pinfunction "I0_5") (pintype "input"))
      (node (ref "R1") (pin "1") (pinfunction "1_1") (pintype "passive"))
      (node (ref "R11") (pin "2") (pinfunction "2_2") (pintype "passive"))
    )
    (net (code "254") (name "~{SDN4}") (class "Default")
      (node (ref "E13") (pin "10") (pinfunction "Y5_10") (pintype "output"))
      (node (ref "E20") (pin "9") (pinfunction "I0_9") (pintype "input"))
    )
    (net (code "255") (name "~{SER4}") (class "Default")
      (node (ref "E13") (pin "11") (pinfunction "Y4_11") (pintype "output"))
      (node (ref "E20") (pin "4") (pinfunction "I0_4") (pintype "input"))
    )
    (net (code "256") (name "~{STR2}") (class "Default")
      (node (ref "E12") (pin "12") (pinfunction "Y3_12") (pintype "output"))
      (node (ref "E20") (pin "1") (pinfunction "I0_1") (pintype "input"))
    )
    (net (code "257") (name "~{TR_SKIP}") (class "Default")
      (node (ref "E19") (pin "1") (pinfunction "CLR_1") (pintype "input"))
      (node (ref "E20") (pin "3") (pinfunction "O_3") (pintype "output"))
      (node (ref "E6") (pin "1") (pinfunction "I0_1") (pintype "input"))
    )
    (net (code "258") (name "~{XDR2}") (class "Default")
      (node (ref "E12") (pin "13") (pinfunction "Y2_13") (pintype "output"))
      (node (ref "E24") (pin "4") (pinfunction "I0_4") (pintype "input"))
      (node (ref "E25") (pin "9") (pinfunction "I_9") (pintype "input"))
      (node (ref "E35") (pin "12") (pinfunction "I1_12") (pintype "input"))
      (node (ref "E5") (pin "10") (pinfunction "I1_10") (pintype "input"))
      (node (ref "E5") (pin "9") (pinfunction "I0_9") (pintype "input"))
    )
  )
)
